# S7G7_footprint_simplified_w_ethernet_v1p.net
KiCad netlist of a schematic drawn in EAGLE
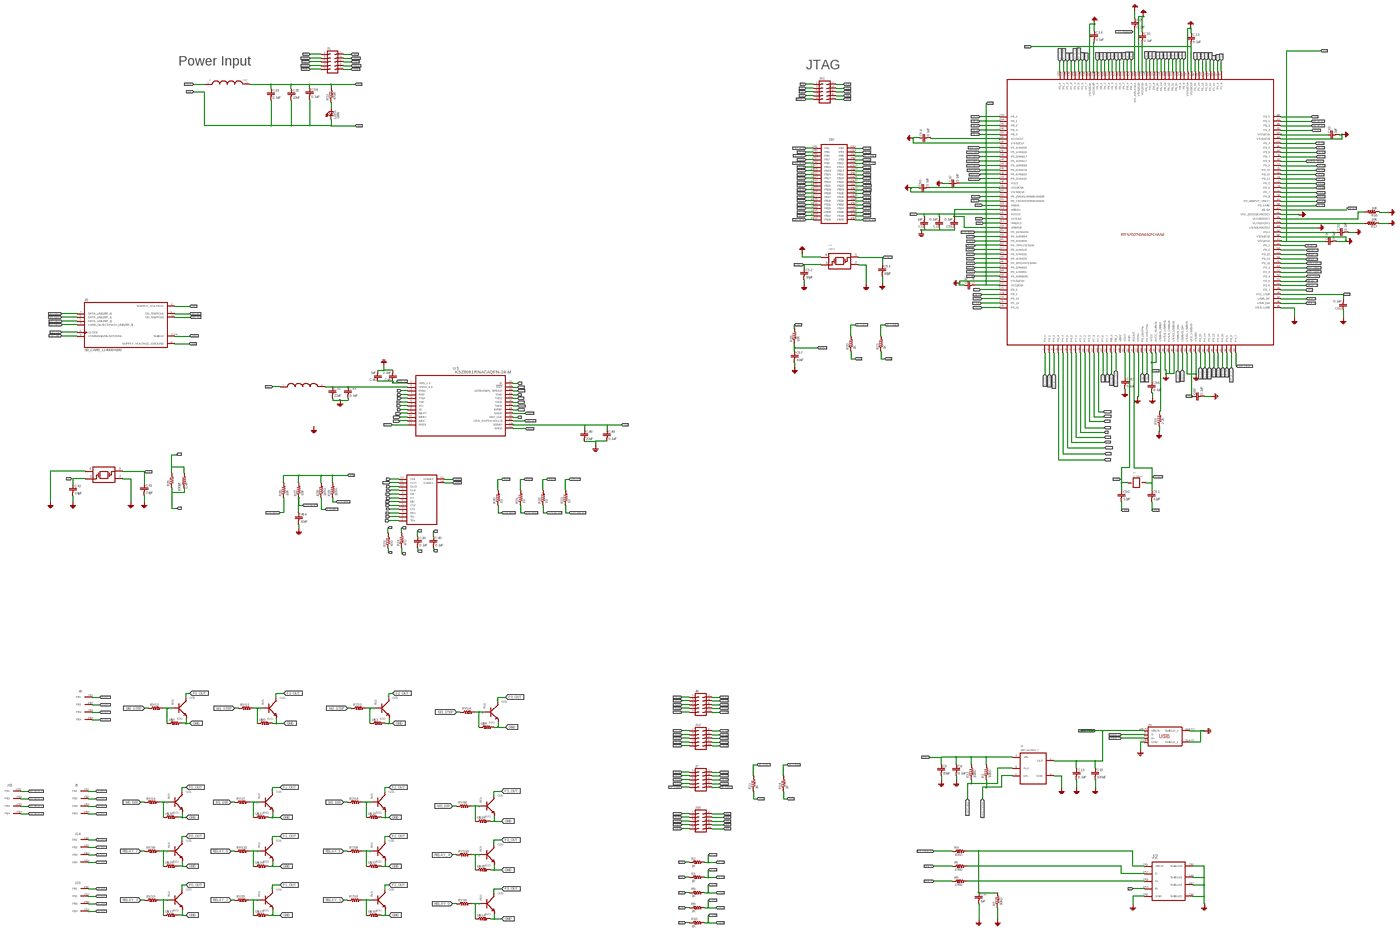
[diagram p0: schematic, sheet 1, overview]
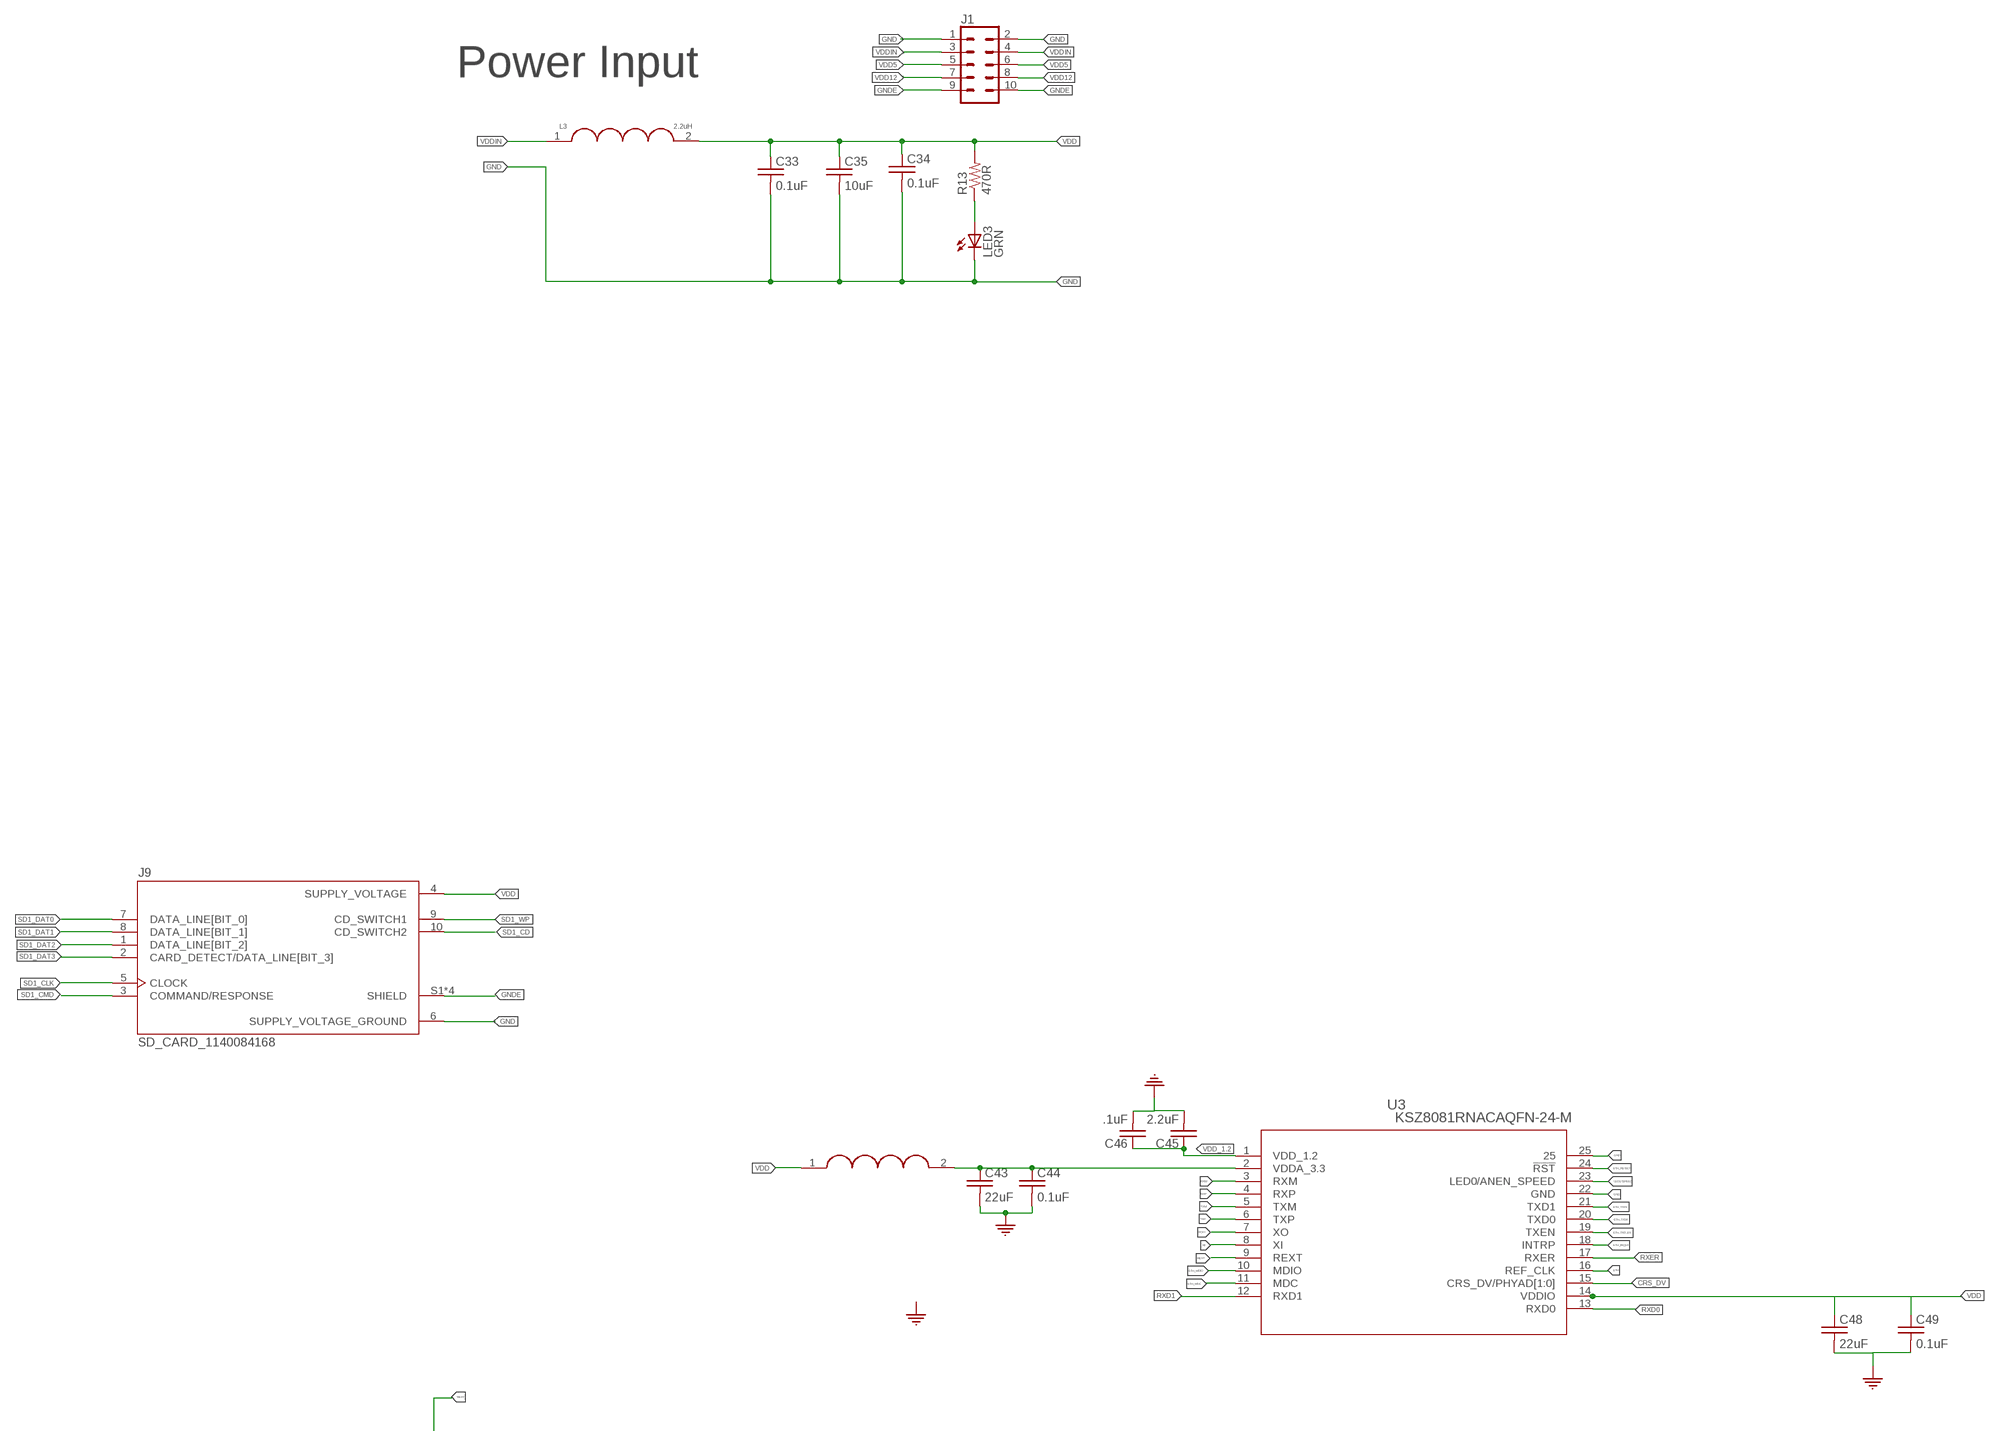
[diagram p1: schematic, sheet 1, part 1 of 4]
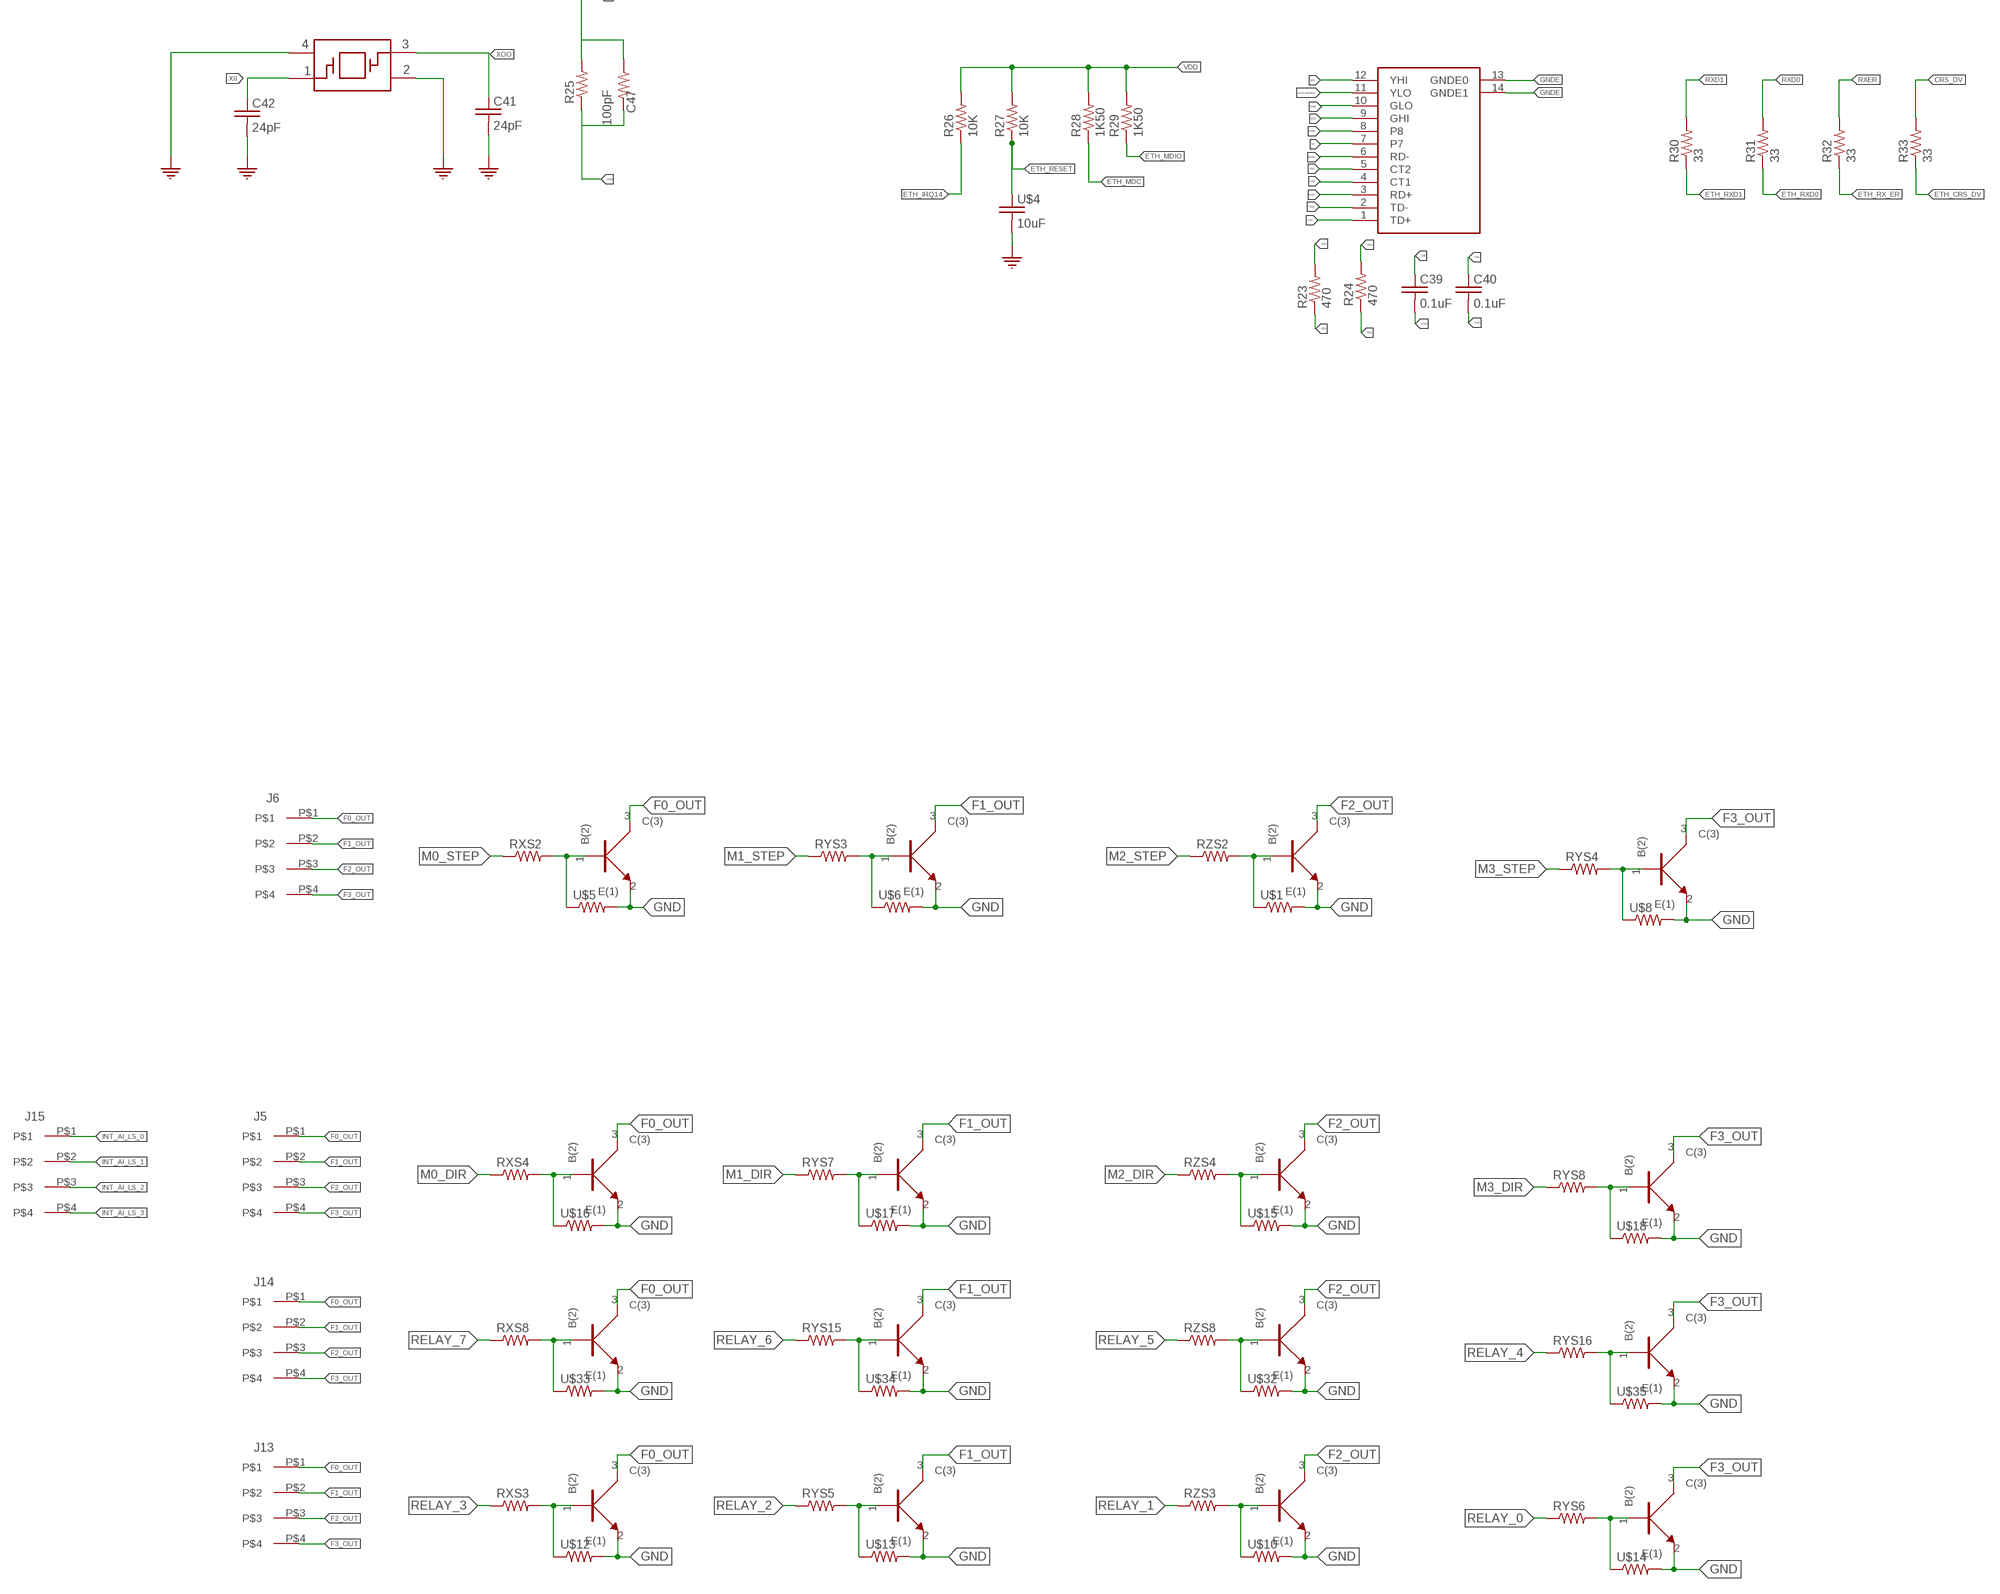
[diagram p2: schematic, sheet 1, part 2 of 4]
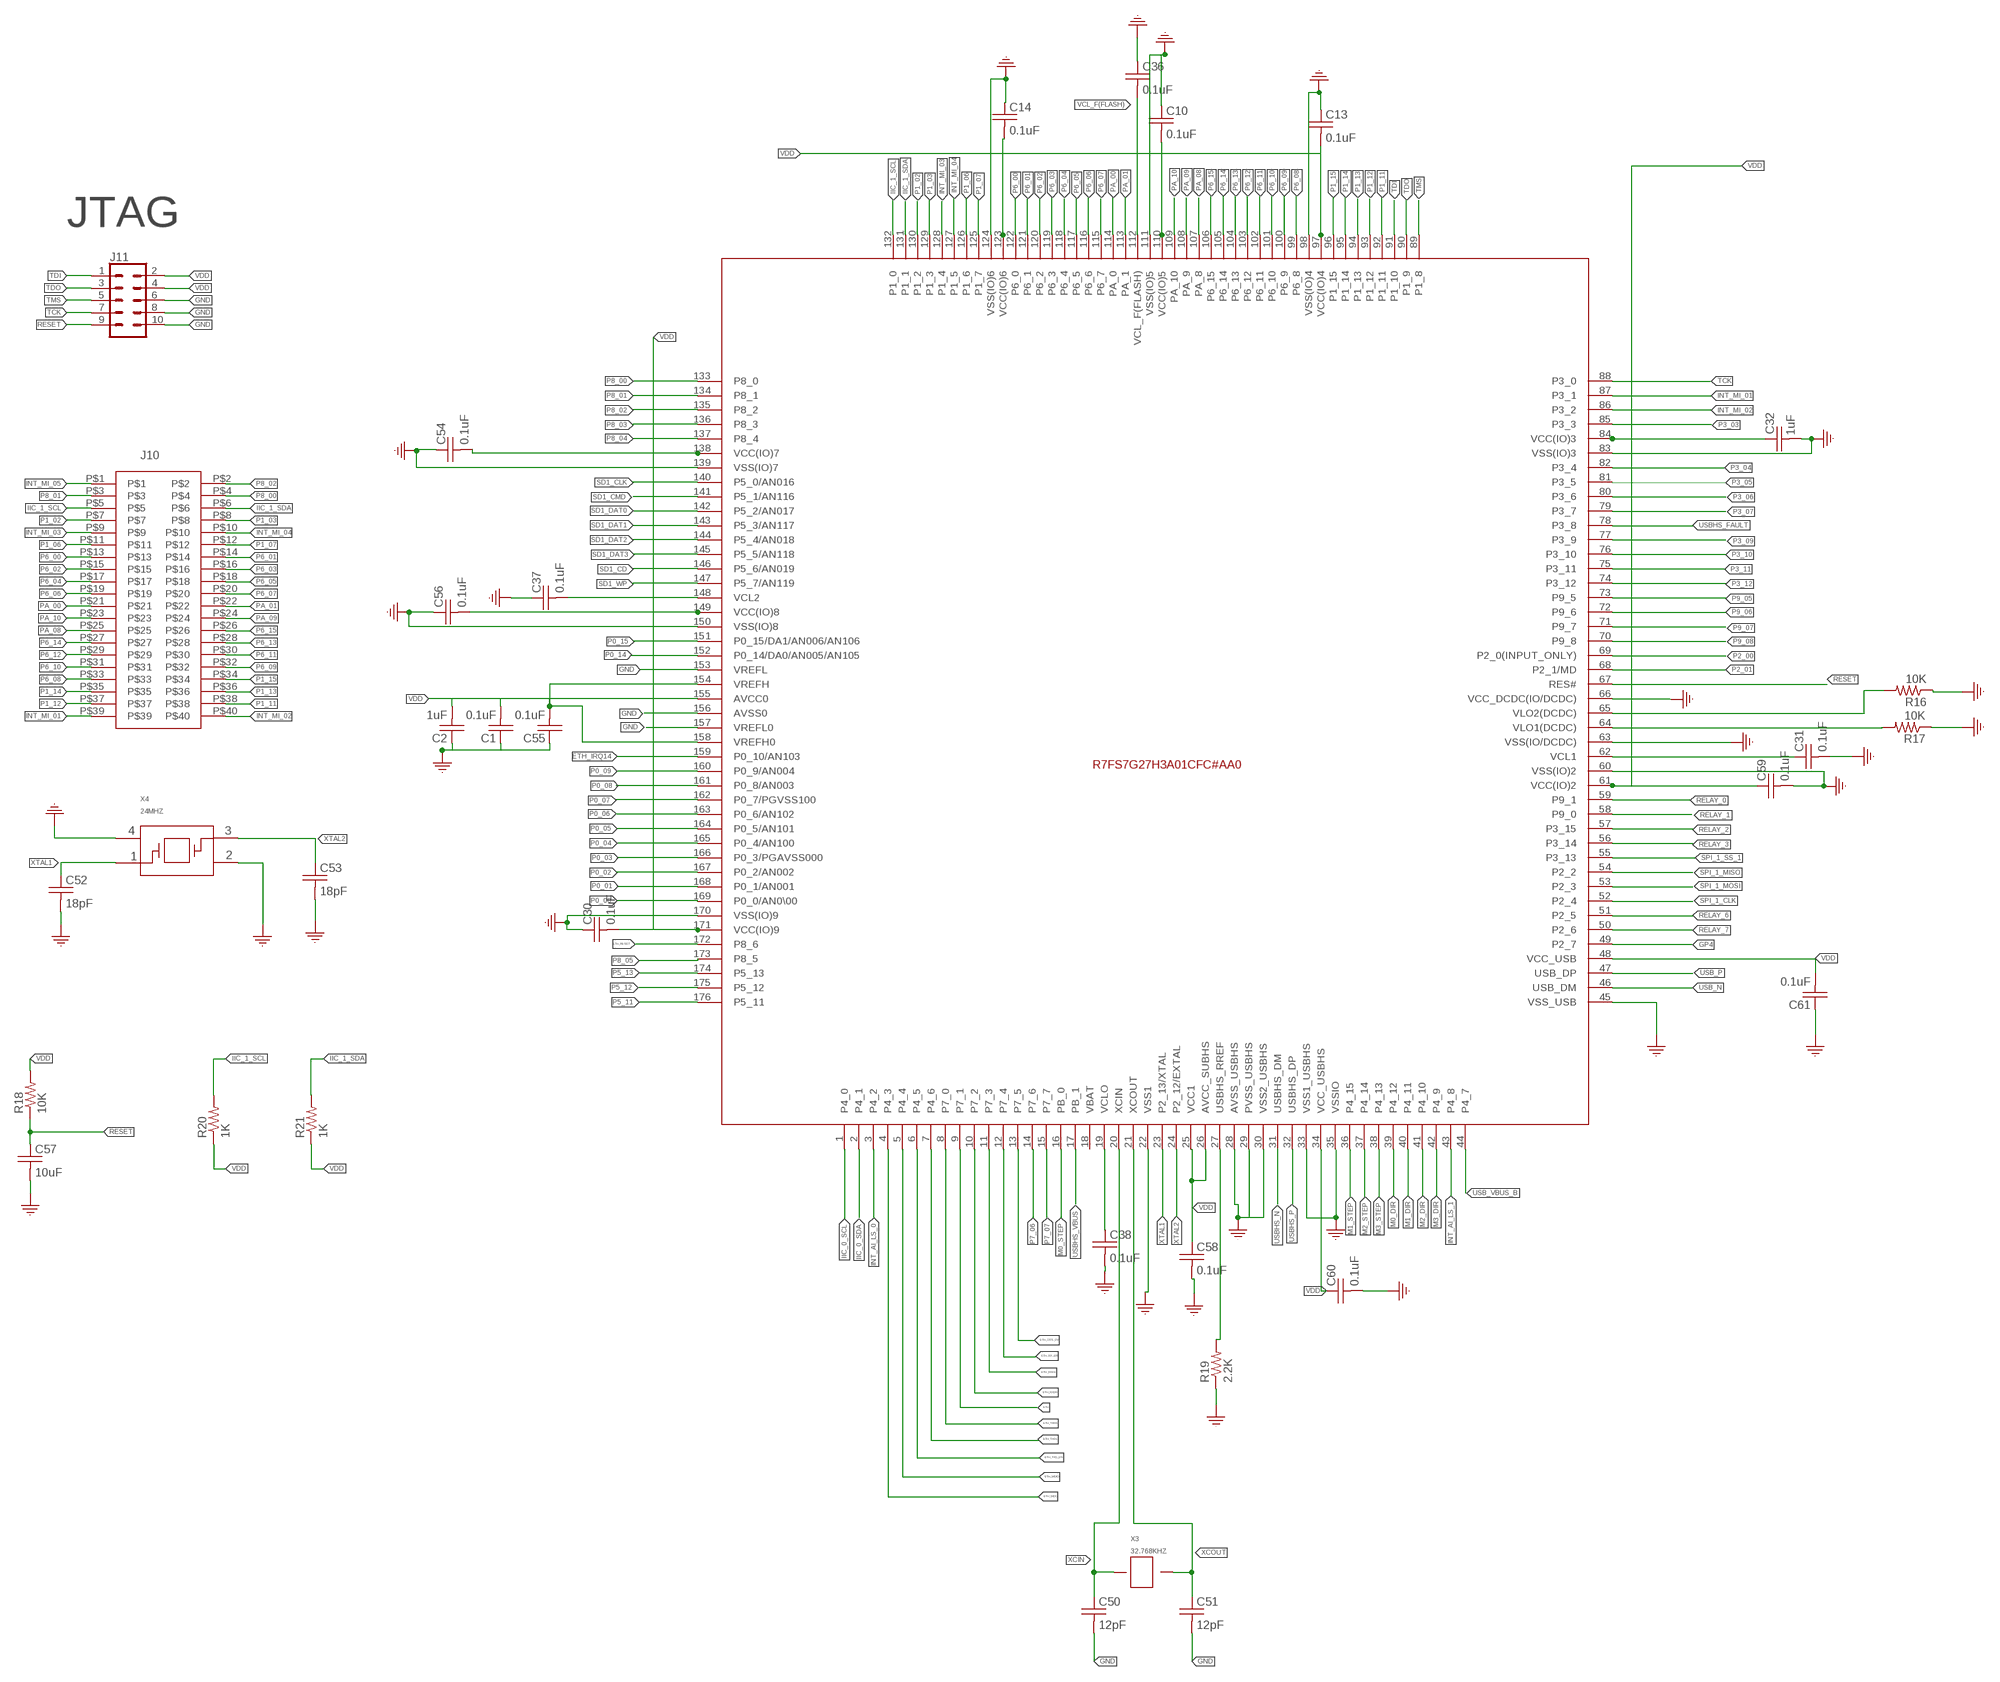
[diagram p3: schematic, sheet 1, part 3 of 4]
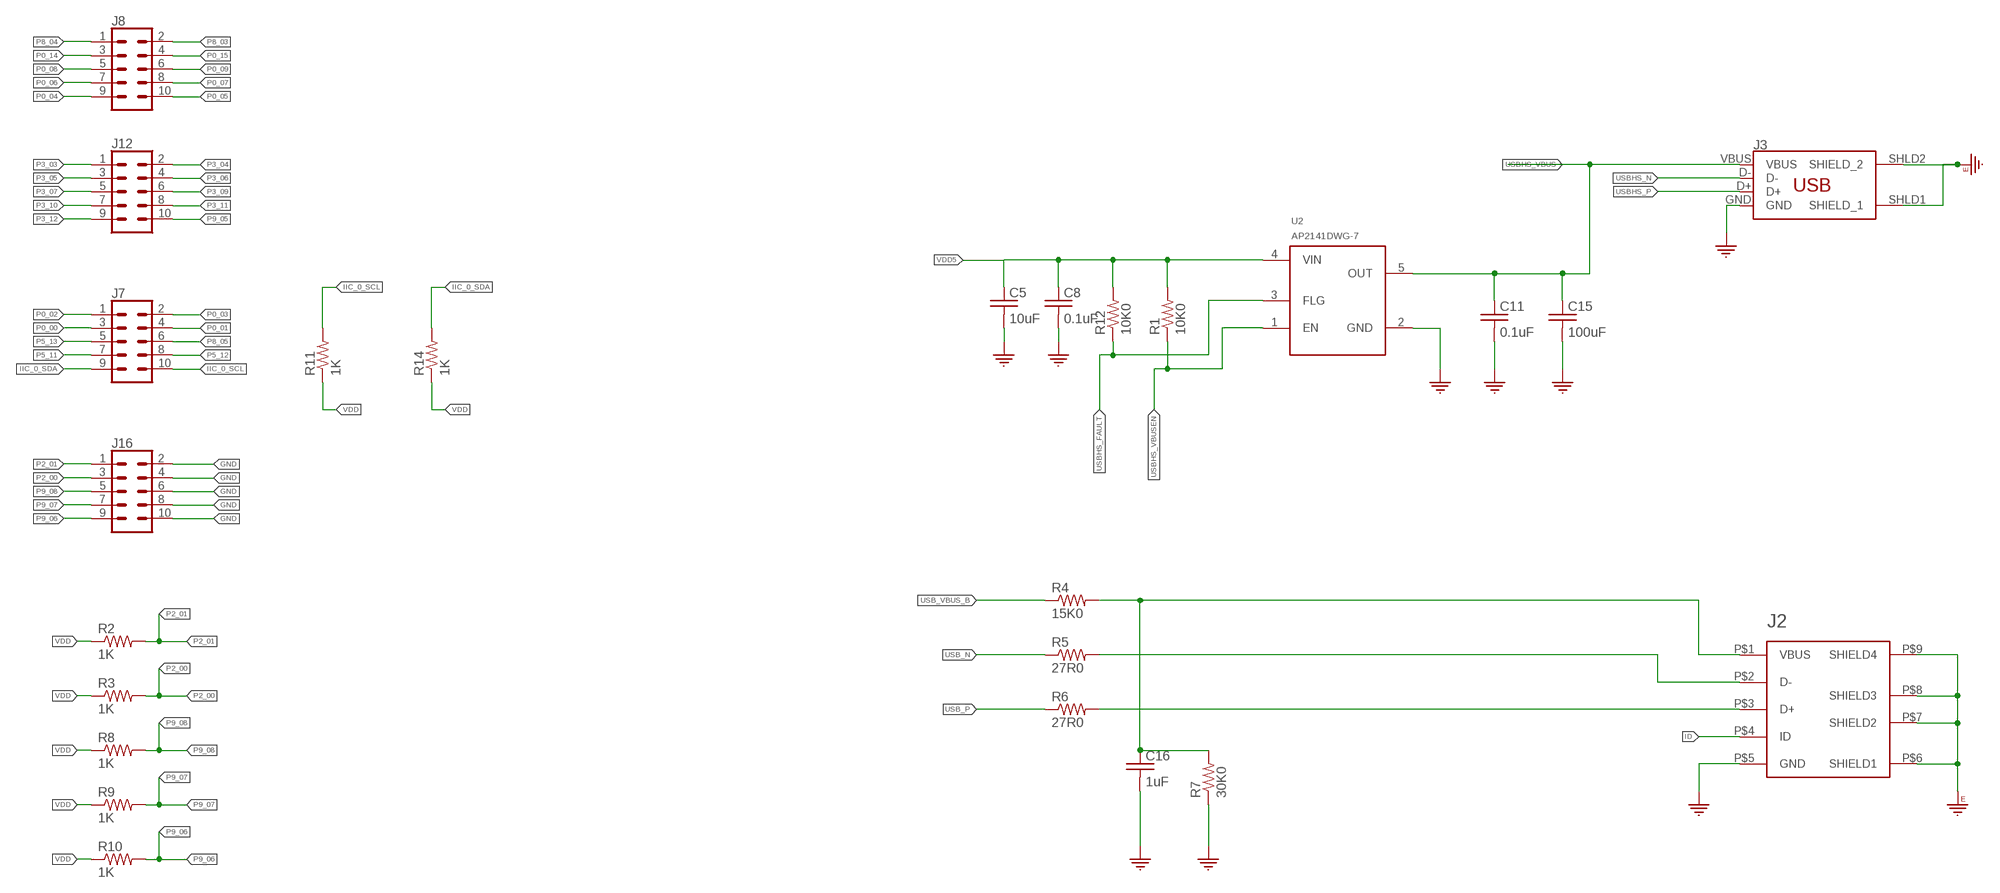
[diagram p4: schematic, sheet 1, part 4 of 4]

(export (version "E")
  (design (tool "Eeschema 10.0.6"))
  (components
    (comp (ref "C1")
      (value "0.1uF")
      (footprint "eagle-import:0402")
      (libsource (lib "eagle-import") (part "C_0402"))
    )
    (comp (ref "C2")
      (value "1uF")
      (footprint "eagle-import:0402")
      (libsource (lib "eagle-import") (part "C_0402"))
    )
    (comp (ref "C5")
      (value "10uF")
      (footprint "eagle-import:0402")
      (libsource (lib "eagle-import") (part "C_0402"))
    )
    (comp (ref "C8")
      (value "0.1uF")
      (footprint "eagle-import:0402")
      (libsource (lib "eagle-import") (part "C_0402"))
    )
    (comp (ref "C10")
      (value "0.1uF")
      (footprint "eagle-import:0402")
      (libsource (lib "eagle-import") (part "C_0402"))
    )
    (comp (ref "C11")
      (value "0.1uF")
      (footprint "eagle-import:0402")
      (libsource (lib "eagle-import") (part "C_0402"))
    )
    (comp (ref "C13")
      (value "0.1uF")
      (footprint "eagle-import:0402")
      (libsource (lib "eagle-import") (part "C_0402"))
    )
    (comp (ref "C14")
      (value "0.1uF")
      (footprint "eagle-import:0402")
      (libsource (lib "eagle-import") (part "C_0402"))
    )
    (comp (ref "C15")
      (value "100uF")
      (footprint "eagle-import:C1210")
      (libsource (lib "eagle-import") (part "C_1210"))
    )
    (comp (ref "C16")
      (value "1uF")
      (footprint "eagle-import:0402")
      (libsource (lib "eagle-import") (part "C_0402"))
    )
    (comp (ref "C30")
      (value "0.1uF")
      (footprint "eagle-import:0402")
      (libsource (lib "eagle-import") (part "C_0402"))
    )
    (comp (ref "C31")
      (value "0.1uF")
      (footprint "eagle-import:0402")
      (libsource (lib "eagle-import") (part "C_0402"))
    )
    (comp (ref "C32")
      (value "1uF")
      (footprint "eagle-import:0402")
      (libsource (lib "eagle-import") (part "C_0402"))
    )
    (comp (ref "C33")
      (value "0.1uF")
      (footprint "eagle-import:0402")
      (libsource (lib "eagle-import") (part "C_0402"))
    )
    (comp (ref "C34")
      (value "0.1uF")
      (footprint "eagle-import:0402")
      (libsource (lib "eagle-import") (part "C_0402"))
    )
    (comp (ref "C35")
      (value "10uF")
      (footprint "eagle-import:0402")
      (libsource (lib "eagle-import") (part "C_0402"))
    )
    (comp (ref "C36")
      (value "0.1uF")
      (footprint "eagle-import:0402")
      (libsource (lib "eagle-import") (part "C_0402"))
    )
    (comp (ref "C37")
      (value "0.1uF")
      (footprint "eagle-import:0402")
      (libsource (lib "eagle-import") (part "C_0402"))
    )
    (comp (ref "C38")
      (value "0.1uF")
      (footprint "eagle-import:0402")
      (libsource (lib "eagle-import") (part "C_0402"))
    )
    (comp (ref "C39")
      (value "0.1uF")
      (footprint "eagle-import:0402")
      (libsource (lib "eagle-import") (part "C_0402"))
    )
    (comp (ref "C40")
      (value "0.1uF")
      (footprint "eagle-import:0402")
      (libsource (lib "eagle-import") (part "C_0402"))
    )
    (comp (ref "C41")
      (value "24pF")
      (footprint "eagle-import:0402")
      (libsource (lib "eagle-import") (part "C_0402"))
    )
    (comp (ref "C42")
      (value "24pF")
      (footprint "eagle-import:0402")
      (libsource (lib "eagle-import") (part "C_0402"))
    )
    (comp (ref "C43")
      (value "22uF")
      (footprint "eagle-import:0603")
      (libsource (lib "eagle-import") (part "C_0603"))
    )
    (comp (ref "C44")
      (value "0.1uF")
      (footprint "eagle-import:0402")
      (libsource (lib "eagle-import") (part "C_0402"))
    )
    (comp (ref "C45")
      (value "2.2uF")
      (footprint "eagle-import:0402")
      (libsource (lib "eagle-import") (part "C_0402"))
    )
    (comp (ref "C46")
      (value ".1uF")
      (footprint "eagle-import:0402")
      (libsource (lib "eagle-import") (part "C_0402"))
    )
    (comp (ref "C47")
      (value "100pF")
      (footprint "eagle-import:0402")
      (libsource (lib "eagle-import") (part "R_0402"))
    )
    (comp (ref "C48")
      (value "22uF")
      (footprint "eagle-import:0603")
      (libsource (lib "eagle-import") (part "C_0603"))
    )
    (comp (ref "C49")
      (value "0.1uF")
      (footprint "eagle-import:0402")
      (libsource (lib "eagle-import") (part "C_0402"))
    )
    (comp (ref "C50")
      (value "12pF")
      (footprint "eagle-import:0402")
      (libsource (lib "eagle-import") (part "C_0402"))
    )
    (comp (ref "C51")
      (value "12pF")
      (footprint "eagle-import:0402")
      (libsource (lib "eagle-import") (part "C_0402"))
    )
    (comp (ref "C52")
      (value "18pF")
      (footprint "eagle-import:0402")
      (libsource (lib "eagle-import") (part "C_0402"))
    )
    (comp (ref "C53")
      (value "18pF")
      (footprint "eagle-import:0402")
      (libsource (lib "eagle-import") (part "C_0402"))
    )
    (comp (ref "C54")
      (value "0.1uF")
      (footprint "eagle-import:0402")
      (libsource (lib "eagle-import") (part "C_0402"))
    )
    (comp (ref "C55")
      (value "0.1uF")
      (footprint "eagle-import:0402")
      (libsource (lib "eagle-import") (part "C_0402"))
    )
    (comp (ref "C56")
      (value "0.1uF")
      (footprint "eagle-import:0402")
      (libsource (lib "eagle-import") (part "C_0402"))
    )
    (comp (ref "C57")
      (value "10uF")
      (footprint "eagle-import:0402")
      (libsource (lib "eagle-import") (part "C_0402"))
    )
    (comp (ref "C58")
      (value "0.1uF")
      (footprint "eagle-import:0402")
      (libsource (lib "eagle-import") (part "C_0402"))
    )
    (comp (ref "C59")
      (value "0.1uF")
      (footprint "eagle-import:0402")
      (libsource (lib "eagle-import") (part "C_0402"))
    )
    (comp (ref "C60")
      (value "0.1uF")
      (footprint "eagle-import:0402")
      (libsource (lib "eagle-import") (part "C_0402"))
    )
    (comp (ref "C61")
      (value "0.1uF")
      (footprint "eagle-import:0402")
      (libsource (lib "eagle-import") (part "C_0402"))
    )
    (comp (ref "FB2/2")
      (value "FB_0805_120_OHM")
      (footprint "eagle-import:0805")
      (libsource (lib "eagle-import") (part "FB_0805_120_OHM"))
    )
    (comp (ref "J1")
      (value "CONN_05X2PTH")
      (footprint "eagle-import:2X5")
      (libsource (lib "eagle-import") (part "CONN_05X2PTH"))
    )
    (comp (ref "J2")
      (value "USB_MICRO-B")
      (footprint "eagle-import:USB_MICRO-B")
      (libsource (lib "eagle-import") (part "USB_MICRO-B"))
    )
    (comp (ref "J3")
      (value "USB_A")
      (footprint "eagle-import:USB_A_SMT")
      (libsource (lib "eagle-import") (part "USB_A"))
    )
    (comp (ref "J4")
      (value "RJ45_WITH_ELEC")
      (footprint "eagle-import:RJ45_TH_ELEC")
      (libsource (lib "eagle-import") (part "RJ45_WITH_ELEC"))
    )
    (comp (ref "J5")
      (value "3.81MM_1_X_4_RT_ANGLE_PLUG_HEADER")
      (footprint "eagle-import:1X4_3.81MM_PITCH")
      (libsource (lib "eagle-import") (part "3.81MM_1_X_4_RT_ANGLE_PLUG_HEADER"))
    )
    (comp (ref "J6")
      (value "3.81MM_1_X_4_RT_ANGLE_PLUG_HEADER")
      (footprint "eagle-import:1X4_3.81MM_PITCH")
      (libsource (lib "eagle-import") (part "3.81MM_1_X_4_RT_ANGLE_PLUG_HEADER"))
    )
    (comp (ref "J7")
      (value "CONN_05X2NO_SILK")
      (footprint "eagle-import:2X5_NOSILK")
      (libsource (lib "eagle-import") (part "CONN_05X2NO_SILK"))
    )
    (comp (ref "J8")
      (value "CONN_05X2NO_SILK")
      (footprint "eagle-import:2X5_NOSILK")
      (libsource (lib "eagle-import") (part "CONN_05X2NO_SILK"))
    )
    (comp (ref "J9")
      (value "SD_CARD_1140084168")
      (footprint "eagle-import:AMPHENOL_1140084168")
      (fields
        (field (name "DIGI-KEY_PART_NUMBER") "114-00841-68-1-ND")
        (field (name "MF") "Amphenol ICC")
        (field (name "MP") "114-00841-68")
      )
      (libsource (lib "eagle-import") (part "SD_CARD_1140084168"))
    )
    (comp (ref "J10")
      (value "HEADER_2_X_20_GENERIC")
      (footprint "eagle-import:HEADER_2_X_20_.1_INCH")
      (libsource (lib "eagle-import") (part "HEADER_2_X_20_GENERIC"))
    )
    (comp (ref "J11")
      (value "CONN_05X2PTH")
      (footprint "eagle-import:2X5")
      (libsource (lib "eagle-import") (part "CONN_05X2PTH"))
    )
    (comp (ref "J12")
      (value "CONN_05X2NO_SILK")
      (footprint "eagle-import:2X5_NOSILK")
      (libsource (lib "eagle-import") (part "CONN_05X2NO_SILK"))
    )
    (comp (ref "J13")
      (value "3.81MM_1_X_4_RT_ANGLE_PLUG_HEADER")
      (footprint "eagle-import:1X4_3.81MM_PITCH")
      (libsource (lib "eagle-import") (part "3.81MM_1_X_4_RT_ANGLE_PLUG_HEADER"))
    )
    (comp (ref "J14")
      (value "3.81MM_1_X_4_RT_ANGLE_PLUG_HEADER")
      (footprint "eagle-import:1X4_3.81MM_PITCH")
      (libsource (lib "eagle-import") (part "3.81MM_1_X_4_RT_ANGLE_PLUG_HEADER"))
    )
    (comp (ref "J15")
      (value "3.81MM_1_X_4_RT_ANGLE_PLUG_HEADER")
      (footprint "eagle-import:1X4_3.81MM_PITCH")
      (libsource (lib "eagle-import") (part "3.81MM_1_X_4_RT_ANGLE_PLUG_HEADER"))
    )
    (comp (ref "J16")
      (value "CONN_05X2SHD_SMD")
      (footprint "eagle-import:2X5-SHROUDED_SMD")
      (libsource (lib "eagle-import") (part "CONN_05X2SHD_SMD"))
    )
    (comp (ref "L3")
      (value "2.2uH")
      (footprint "eagle-import:1008_(2520_METRIC)")
      (libsource (lib "eagle-import") (part "INDUCTOR_1008_2.2_MH_1.3A"))
    )
    (comp (ref "LED3")
      (value "LED_0805_GREEN")
      (footprint "eagle-import:LED_0805_GREEN")
      (libsource (lib "eagle-import") (part "LED_0805_GREEN"))
    )
    (comp (ref "R1")
      (value "10K0")
      (footprint "eagle-import:0402")
      (libsource (lib "eagle-import") (part "R_0402"))
    )
    (comp (ref "R2")
      (value "1K")
      (footprint "eagle-import:0402")
      (libsource (lib "eagle-import") (part "R_0402"))
    )
    (comp (ref "R3")
      (value "1K")
      (footprint "eagle-import:0402")
      (libsource (lib "eagle-import") (part "R_0402"))
    )
    (comp (ref "R4")
      (value "15K0")
      (footprint "eagle-import:0402")
      (libsource (lib "eagle-import") (part "R_0402"))
    )
    (comp (ref "R5")
      (value "27R0")
      (footprint "eagle-import:0402")
      (libsource (lib "eagle-import") (part "R_0402"))
    )
    (comp (ref "R6")
      (value "27R0")
      (footprint "eagle-import:0402")
      (libsource (lib "eagle-import") (part "R_0402"))
    )
    (comp (ref "R7")
      (value "30K0")
      (footprint "eagle-import:0402")
      (libsource (lib "eagle-import") (part "R_0402"))
    )
    (comp (ref "R8")
      (value "1K")
      (footprint "eagle-import:0402")
      (libsource (lib "eagle-import") (part "R_0402"))
    )
    (comp (ref "R9")
      (value "1K")
      (footprint "eagle-import:0402")
      (libsource (lib "eagle-import") (part "R_0402"))
    )
    (comp (ref "R10")
      (value "1K")
      (footprint "eagle-import:0402")
      (libsource (lib "eagle-import") (part "R_0402"))
    )
    (comp (ref "R11")
      (value "1K")
      (footprint "eagle-import:0402")
      (libsource (lib "eagle-import") (part "R_0402"))
    )
    (comp (ref "R12")
      (value "10K0")
      (footprint "eagle-import:0402")
      (libsource (lib "eagle-import") (part "R_0402"))
    )
    (comp (ref "R13")
      (value "470R")
      (footprint "eagle-import:0402")
      (libsource (lib "eagle-import") (part "R_0402"))
    )
    (comp (ref "R14")
      (value "1K")
      (footprint "eagle-import:0402")
      (libsource (lib "eagle-import") (part "R_0402"))
    )
    (comp (ref "R16")
      (value "10K")
      (footprint "eagle-import:0402")
      (libsource (lib "eagle-import") (part "R_0402"))
    )
    (comp (ref "R17")
      (value "10K")
      (footprint "eagle-import:0402")
      (libsource (lib "eagle-import") (part "R_0402"))
    )
    (comp (ref "R18")
      (value "10K")
      (footprint "eagle-import:0402")
      (libsource (lib "eagle-import") (part "R_0402"))
    )
    (comp (ref "R19")
      (value "2.2K")
      (footprint "eagle-import:0402")
      (libsource (lib "eagle-import") (part "R_0402"))
    )
    (comp (ref "R20")
      (value "1K")
      (footprint "eagle-import:0402")
      (libsource (lib "eagle-import") (part "R_0402"))
    )
    (comp (ref "R21")
      (value "1K")
      (footprint "eagle-import:0402")
      (libsource (lib "eagle-import") (part "R_0402"))
    )
    (comp (ref "R23")
      (value "470")
      (footprint "eagle-import:0402")
      (libsource (lib "eagle-import") (part "R_0402"))
    )
    (comp (ref "R24")
      (value "470")
      (footprint "eagle-import:0402")
      (libsource (lib "eagle-import") (part "R_0402"))
    )
    (comp (ref "R25")
      (value "6k49")
      (footprint "eagle-import:0402")
      (libsource (lib "eagle-import") (part "R_0402"))
    )
    (comp (ref "R26")
      (value "10K")
      (footprint "eagle-import:0402")
      (libsource (lib "eagle-import") (part "R_0402"))
    )
    (comp (ref "R27")
      (value "10K")
      (footprint "eagle-import:0402")
      (libsource (lib "eagle-import") (part "R_0402"))
    )
    (comp (ref "R28")
      (value "1K50")
      (footprint "eagle-import:0402")
      (libsource (lib "eagle-import") (part "R_0402"))
    )
    (comp (ref "R29")
      (value "1K50")
      (footprint "eagle-import:0402")
      (libsource (lib "eagle-import") (part "R_0402"))
    )
    (comp (ref "R30")
      (value "33")
      (footprint "eagle-import:0402")
      (libsource (lib "eagle-import") (part "R_0402"))
    )
    (comp (ref "R31")
      (value "33")
      (footprint "eagle-import:0402")
      (libsource (lib "eagle-import") (part "R_0402"))
    )
    (comp (ref "R32")
      (value "33")
      (footprint "eagle-import:0402")
      (libsource (lib "eagle-import") (part "R_0402"))
    )
    (comp (ref "R33")
      (value "33")
      (footprint "eagle-import:0402")
      (libsource (lib "eagle-import") (part "R_0402"))
    )
    (comp (ref "RXS2")
      (value "1K")
      (footprint "eagle-import:0402")
      (libsource (lib "eagle-import") (part "R_0402"))
    )
    (comp (ref "RXS3")
      (value "1K")
      (footprint "eagle-import:0402")
      (libsource (lib "eagle-import") (part "R_0402"))
    )
    (comp (ref "RXS4")
      (value "1K")
      (footprint "eagle-import:0402")
      (libsource (lib "eagle-import") (part "R_0402"))
    )
    (comp (ref "RXS8")
      (value "1K")
      (footprint "eagle-import:0402")
      (libsource (lib "eagle-import") (part "R_0402"))
    )
    (comp (ref "RYS3")
      (value "1K")
      (footprint "eagle-import:0402")
      (libsource (lib "eagle-import") (part "R_0402"))
    )
    (comp (ref "RYS4")
      (value "1K")
      (footprint "eagle-import:0402")
      (libsource (lib "eagle-import") (part "R_0402"))
    )
    (comp (ref "RYS5")
      (value "1K")
      (footprint "eagle-import:0402")
      (libsource (lib "eagle-import") (part "R_0402"))
    )
    (comp (ref "RYS6")
      (value "1K")
      (footprint "eagle-import:0402")
      (libsource (lib "eagle-import") (part "R_0402"))
    )
    (comp (ref "RYS7")
      (value "1K")
      (footprint "eagle-import:0402")
      (libsource (lib "eagle-import") (part "R_0402"))
    )
    (comp (ref "RYS8")
      (value "1K")
      (footprint "eagle-import:0402")
      (libsource (lib "eagle-import") (part "R_0402"))
    )
    (comp (ref "RYS15")
      (value "1K")
      (footprint "eagle-import:0402")
      (libsource (lib "eagle-import") (part "R_0402"))
    )
    (comp (ref "RYS16")
      (value "1K")
      (footprint "eagle-import:0402")
      (libsource (lib "eagle-import") (part "R_0402"))
    )
    (comp (ref "RZS2")
      (value "1K")
      (footprint "eagle-import:0402")
      (libsource (lib "eagle-import") (part "R_0402"))
    )
    (comp (ref "RZS3")
      (value "1K")
      (footprint "eagle-import:0402")
      (libsource (lib "eagle-import") (part "R_0402"))
    )
    (comp (ref "RZS4")
      (value "1K")
      (footprint "eagle-import:0402")
      (libsource (lib "eagle-import") (part "R_0402"))
    )
    (comp (ref "RZS8")
      (value "1K")
      (footprint "eagle-import:0402")
      (libsource (lib "eagle-import") (part "R_0402"))
    )
    (comp (ref "U$1")
      (value "1K")
      (footprint "eagle-import:0402")
      (libsource (lib "eagle-import") (part "R_0402"))
    )
    (comp (ref "U$3")
      (value "XTAL_25_MHZ")
      (footprint "eagle-import:SMD_3225")
      (libsource (lib "eagle-import") (part "XTAL_25_MHZ"))
    )
    (comp (ref "U$4")
      (value "10uF")
      (footprint "eagle-import:0402")
      (libsource (lib "eagle-import") (part "C_0402"))
    )
    (comp (ref "U$5")
      (value "1K")
      (footprint "eagle-import:0402")
      (libsource (lib "eagle-import") (part "R_0402"))
    )
    (comp (ref "U$6")
      (value "1K")
      (footprint "eagle-import:0402")
      (libsource (lib "eagle-import") (part "R_0402"))
    )
    (comp (ref "U$8")
      (value "1K")
      (footprint "eagle-import:0402")
      (libsource (lib "eagle-import") (part "R_0402"))
    )
    (comp (ref "U$10")
      (value "1K")
      (footprint "eagle-import:0402")
      (libsource (lib "eagle-import") (part "R_0402"))
    )
    (comp (ref "U$12")
      (value "1K")
      (footprint "eagle-import:0402")
      (libsource (lib "eagle-import") (part "R_0402"))
    )
    (comp (ref "U$13")
      (value "1K")
      (footprint "eagle-import:0402")
      (libsource (lib "eagle-import") (part "R_0402"))
    )
    (comp (ref "U$14")
      (value "1K")
      (footprint "eagle-import:0402")
      (libsource (lib "eagle-import") (part "R_0402"))
    )
    (comp (ref "U$15")
      (value "1K")
      (footprint "eagle-import:0402")
      (libsource (lib "eagle-import") (part "R_0402"))
    )
    (comp (ref "U$16")
      (value "1K")
      (footprint "eagle-import:0402")
      (libsource (lib "eagle-import") (part "R_0402"))
    )
    (comp (ref "U$17")
      (value "1K")
      (footprint "eagle-import:0402")
      (libsource (lib "eagle-import") (part "R_0402"))
    )
    (comp (ref "U$18")
      (value "1K")
      (footprint "eagle-import:0402")
      (libsource (lib "eagle-import") (part "R_0402"))
    )
    (comp (ref "U$32")
      (value "1K")
      (footprint "eagle-import:0402")
      (libsource (lib "eagle-import") (part "R_0402"))
    )
    (comp (ref "U$33")
      (value "1K")
      (footprint "eagle-import:0402")
      (libsource (lib "eagle-import") (part "R_0402"))
    )
    (comp (ref "U$34")
      (value "1K")
      (footprint "eagle-import:0402")
      (libsource (lib "eagle-import") (part "R_0402"))
    )
    (comp (ref "U$35")
      (value "1K")
      (footprint "eagle-import:0402")
      (libsource (lib "eagle-import") (part "R_0402"))
    )
    (comp (ref "U2")
      (value "AP2141DWG-5")
      (footprint "eagle-import:SOT-23-5")
      (libsource (lib "eagle-import") (part "AP2141DWG-5"))
    )
    (comp (ref "U3")
      (value "KSZ8081RNACAQFN-24-M")
      (footprint "eagle-import:QFN-24-M")
      (fields (field (name "MANUFACTURER_PART_NUMBER") "KSZ8081RNACA"))
      (libsource (lib "eagle-import") (part "KSZ8081RNACAQFN-24-M"))
    )
    (comp (ref "U4")
      (value "S7G2_X_176")
      (footprint "eagle-import:LQFP176_24X24")
      (libsource (lib "eagle-import") (part "S7G2_X_176"))
    )
    (comp (ref "U7")
      (value "BC846BW")
      (footprint "eagle-import:SOT323")
      (libsource (lib "eagle-import") (part "BC846BW"))
    )
    (comp (ref "U8")
      (value "BC846BW")
      (footprint "eagle-import:SOT323")
      (libsource (lib "eagle-import") (part "BC846BW"))
    )
    (comp (ref "U9")
      (value "BC846BW")
      (footprint "eagle-import:SOT323")
      (libsource (lib "eagle-import") (part "BC846BW"))
    )
    (comp (ref "U10")
      (value "BC846BW")
      (footprint "eagle-import:SOT323")
      (libsource (lib "eagle-import") (part "BC846BW"))
    )
    (comp (ref "U12")
      (value "BC846BW")
      (footprint "eagle-import:SOT323")
      (libsource (lib "eagle-import") (part "BC846BW"))
    )
    (comp (ref "U13")
      (value "BC846BW")
      (footprint "eagle-import:SOT323")
      (libsource (lib "eagle-import") (part "BC846BW"))
    )
    (comp (ref "U14")
      (value "BC846BW")
      (footprint "eagle-import:SOT323")
      (libsource (lib "eagle-import") (part "BC846BW"))
    )
    (comp (ref "U15")
      (value "BC846BW")
      (footprint "eagle-import:SOT323")
      (libsource (lib "eagle-import") (part "BC846BW"))
    )
    (comp (ref "U16")
      (value "BC846BW")
      (footprint "eagle-import:SOT323")
      (libsource (lib "eagle-import") (part "BC846BW"))
    )
    (comp (ref "U17")
      (value "BC846BW")
      (footprint "eagle-import:SOT323")
      (libsource (lib "eagle-import") (part "BC846BW"))
    )
    (comp (ref "U18")
      (value "BC846BW")
      (footprint "eagle-import:SOT323")
      (libsource (lib "eagle-import") (part "BC846BW"))
    )
    (comp (ref "U19")
      (value "BC846BW")
      (footprint "eagle-import:SOT323")
      (libsource (lib "eagle-import") (part "BC846BW"))
    )
    (comp (ref "U32")
      (value "BC846BW")
      (footprint "eagle-import:SOT323")
      (libsource (lib "eagle-import") (part "BC846BW"))
    )
    (comp (ref "U33")
      (value "BC846BW")
      (footprint "eagle-import:SOT323")
      (libsource (lib "eagle-import") (part "BC846BW"))
    )
    (comp (ref "U34")
      (value "BC846BW")
      (footprint "eagle-import:SOT323")
      (libsource (lib "eagle-import") (part "BC846BW"))
    )
    (comp (ref "U35")
      (value "BC846BW")
      (footprint "eagle-import:SOT323")
      (libsource (lib "eagle-import") (part "BC846BW"))
    )
    (comp (ref "X3")
      (value "32.768KHZ")
      (footprint "eagle-import:SMD_X_2_PADS")
      (libsource (lib "eagle-import") (part "XTAL_32.768KHZ"))
    )
    (comp (ref "X4")
      (value "24MHZ")
      (footprint "eagle-import:SMD_3225")
      (libsource (lib "eagle-import") (part "XTAL_24_MHZ"))
    )
  )
  (nets
    (net (code "1") (name "C58") (class "Default")
      (node (ref "C39") (pin "P$1") (pinfunction "1_P$1") (pintype "passive"))
      (node (ref "J4") (pin "4") (pinfunction "CT1_4") (pintype "bidirectional"))
    )
    (net (code "2") (name "C60") (class "Default")
      (node (ref "C40") (pin "P$1") (pinfunction "1_P$1") (pintype "passive"))
      (node (ref "J4") (pin "5") (pinfunction "CT2_5") (pintype "bidirectional"))
    )
    (net (code "3") (name "CRS_DV") (class "Default")
      (node (ref "R33") (pin "P$2") (pinfunction "2_P$2") (pintype "passive"))
      (node (ref "U3") (pin "15") (pinfunction "CRS_DV/PHYAD[1:0]_15") (pintype "bidirectional"))
    )
    (net (code "4") (name "ETH") (class "Default")
      (node (ref "U3") (pin "16") (pinfunction "REF_CLK_16") (pintype "bidirectional"))
      (node (ref "U4") (pin "9") (pinfunction "P7_1_9") (pintype "bidirectional"))
    )
    (net (code "5") (name "ETH_CRS_DV") (class "Default")
      (node (ref "R33") (pin "P$1") (pinfunction "1_P$1") (pintype "passive"))
      (node (ref "U4") (pin "13") (pinfunction "P7_5_13") (pintype "bidirectional"))
    )
    (net (code "6") (name "ETH_IRQ14") (class "Default")
      (node (ref "R26") (pin "P$1") (pinfunction "1_P$1") (pintype "passive"))
      (node (ref "U3") (pin "18") (pinfunction "INTRP_18") (pintype "bidirectional"))
      (node (ref "U4") (pin "159") (pinfunction "P0_10/AN103_159") (pintype "bidirectional"))
    )
    (net (code "7") (name "ETH_MDC") (class "Default")
      (node (ref "R28") (pin "P$1") (pinfunction "1_P$1") (pintype "passive"))
      (node (ref "U3") (pin "11") (pinfunction "MDC_11") (pintype "input"))
      (node (ref "U4") (pin "4") (pinfunction "P4_3_4") (pintype "bidirectional"))
    )
    (net (code "8") (name "ETH_MDIO") (class "Default")
      (node (ref "R29") (pin "P$1") (pinfunction "1_P$1") (pintype "passive"))
      (node (ref "U3") (pin "10") (pinfunction "MDIO_10") (pintype "bidirectional"))
      (node (ref "U4") (pin "5") (pinfunction "P4_4_5") (pintype "bidirectional"))
    )
    (net (code "9") (name "ETH_RESET") (class "Default")
      (node (ref "R27") (pin "P$1") (pinfunction "1_P$1") (pintype "passive"))
      (node (ref "U$4") (pin "P$1") (pinfunction "1_P$1") (pintype "passive"))
      (node (ref "U3") (pin "24") (pinfunction "~{RST}_24") (pintype "input"))
      (node (ref "U4") (pin "172") (pinfunction "P8_6_172") (pintype "bidirectional"))
    )
    (net (code "10") (name "ETH_RXD0") (class "Default")
      (node (ref "R31") (pin "P$1") (pinfunction "1_P$1") (pintype "passive"))
      (node (ref "U4") (pin "10") (pinfunction "P7_2_10") (pintype "bidirectional"))
    )
    (net (code "11") (name "ETH_RXD1") (class "Default")
      (node (ref "R30") (pin "P$1") (pinfunction "1_P$1") (pintype "passive"))
      (node (ref "U4") (pin "11") (pinfunction "P7_3_11") (pintype "bidirectional"))
    )
    (net (code "12") (name "ETH_RX_ER") (class "Default")
      (node (ref "R32") (pin "P$1") (pinfunction "1_P$1") (pintype "passive"))
      (node (ref "U4") (pin "12") (pinfunction "P7_4_12") (pintype "bidirectional"))
    )
    (net (code "13") (name "ETH_TXD0") (class "Default")
      (node (ref "U3") (pin "20") (pinfunction "TXD0_20") (pintype "input"))
      (node (ref "U4") (pin "8") (pinfunction "P7_0_8") (pintype "bidirectional"))
    )
    (net (code "14") (name "ETH_TXD1") (class "Default")
      (node (ref "U3") (pin "21") (pinfunction "TXD1_21") (pintype "bidirectional"))
      (node (ref "U4") (pin "7") (pinfunction "P4_6_7") (pintype "bidirectional"))
    )
    (net (code "15") (name "ETH_TXD_EN") (class "Default")
      (node (ref "U3") (pin "19") (pinfunction "TXEN_19") (pintype "input"))
      (node (ref "U4") (pin "6") (pinfunction "P4_5_6") (pintype "bidirectional"))
    )
    (net (code "16") (name "F0_OUT") (class "Default")
      (node (ref "J13") (pin "P$1") (pinfunction "P$1_P$1") (pintype "bidirectional"))
      (node (ref "J14") (pin "P$1") (pinfunction "P$1_P$1") (pintype "bidirectional"))
      (node (ref "J5") (pin "P$1") (pinfunction "P$1_P$1") (pintype "bidirectional"))
      (node (ref "J6") (pin "P$1") (pinfunction "P$1_P$1") (pintype "bidirectional"))
      (node (ref "U13") (pin "3") (pinfunction "C(3)_3") (pintype "input"))
      (node (ref "U17") (pin "3") (pinfunction "C(3)_3") (pintype "input"))
      (node (ref "U33") (pin "3") (pinfunction "C(3)_3") (pintype "input"))
      (node (ref "U8") (pin "3") (pinfunction "C(3)_3") (pintype "input"))
    )
    (net (code "17") (name "F1_OUT") (class "Default")
      (node (ref "J13") (pin "P$2") (pinfunction "P$2_P$2") (pintype "bidirectional"))
      (node (ref "J14") (pin "P$2") (pinfunction "P$2_P$2") (pintype "bidirectional"))
      (node (ref "J5") (pin "P$2") (pinfunction "P$2_P$2") (pintype "bidirectional"))
      (node (ref "J6") (pin "P$2") (pinfunction "P$2_P$2") (pintype "bidirectional"))
      (node (ref "U14") (pin "3") (pinfunction "C(3)_3") (pintype "input"))
      (node (ref "U18") (pin "3") (pinfunction "C(3)_3") (pintype "input"))
      (node (ref "U34") (pin "3") (pinfunction "C(3)_3") (pintype "input"))
      (node (ref "U9") (pin "3") (pinfunction "C(3)_3") (pintype "input"))
    )
    (net (code "18") (name "F2_OUT") (class "Default")
      (node (ref "J13") (pin "P$3") (pinfunction "P$3_P$3") (pintype "bidirectional"))
      (node (ref "J14") (pin "P$3") (pinfunction "P$3_P$3") (pintype "bidirectional"))
      (node (ref "J5") (pin "P$3") (pinfunction "P$3_P$3") (pintype "bidirectional"))
      (node (ref "J6") (pin "P$3") (pinfunction "P$3_P$3") (pintype "bidirectional"))
      (node (ref "U12") (pin "3") (pinfunction "C(3)_3") (pintype "input"))
      (node (ref "U16") (pin "3") (pinfunction "C(3)_3") (pintype "input"))
      (node (ref "U32") (pin "3") (pinfunction "C(3)_3") (pintype "input"))
      (node (ref "U7") (pin "3") (pinfunction "C(3)_3") (pintype "input"))
    )
    (net (code "19") (name "F3_OUT") (class "Default")
      (node (ref "J13") (pin "P$4") (pinfunction "P$4_P$4") (pintype "bidirectional"))
      (node (ref "J14") (pin "P$4") (pinfunction "P$4_P$4") (pintype "bidirectional"))
      (node (ref "J5") (pin "P$4") (pinfunction "P$4_P$4") (pintype "bidirectional"))
      (node (ref "J6") (pin "P$4") (pinfunction "P$4_P$4") (pintype "bidirectional"))
      (node (ref "U10") (pin "3") (pinfunction "C(3)_3") (pintype "input"))
      (node (ref "U15") (pin "3") (pinfunction "C(3)_3") (pintype "input"))
      (node (ref "U19") (pin "3") (pinfunction "C(3)_3") (pintype "input"))
      (node (ref "U35") (pin "3") (pinfunction "C(3)_3") (pintype "input"))
    )
    (net (code "20") (name "GND") (class "Default")
      (node (ref "C1") (pin "P$1") (pinfunction "1_P$1") (pintype "passive"))
      (node (ref "C10") (pin "P$1") (pinfunction "1_P$1") (pintype "passive"))
      (node (ref "C11") (pin "P$2") (pinfunction "2_P$2") (pintype "passive"))
      (node (ref "C13") (pin "P$1") (pinfunction "1_P$1") (pintype "passive"))
      (node (ref "C14") (pin "P$1") (pinfunction "1_P$1") (pintype "passive"))
      (node (ref "C15") (pin "2") (pinfunction "2_2") (pintype "passive"))
      (node (ref "C16") (pin "P$2") (pinfunction "2_P$2") (pintype "passive"))
      (node (ref "C2") (pin "P$1") (pinfunction "1_P$1") (pintype "passive"))
      (node (ref "C30") (pin "P$1") (pinfunction "1_P$1") (pintype "passive"))
      (node (ref "C31") (pin "P$2") (pinfunction "2_P$2") (pintype "passive"))
      (node (ref "C32") (pin "P$2") (pinfunction "2_P$2") (pintype "passive"))
      (node (ref "C33") (pin "P$2") (pinfunction "2_P$2") (pintype "passive"))
      (node (ref "C34") (pin "P$2") (pinfunction "2_P$2") (pintype "passive"))
      (node (ref "C35") (pin "P$2") (pinfunction "2_P$2") (pintype "passive"))
      (node (ref "C36") (pin "P$1") (pinfunction "1_P$1") (pintype "passive"))
      (node (ref "C37") (pin "P$1") (pinfunction "1_P$1") (pintype "passive"))
      (node (ref "C38") (pin "P$2") (pinfunction "2_P$2") (pintype "passive"))
      (node (ref "C39") (pin "P$2") (pinfunction "2_P$2") (pintype "passive"))
      (node (ref "C40") (pin "P$2") (pinfunction "2_P$2") (pintype "passive"))
      (node (ref "C41") (pin "P$2") (pinfunction "2_P$2") (pintype "passive"))
      (node (ref "C42") (pin "P$2") (pinfunction "2_P$2") (pintype "passive"))
      (node (ref "C43") (pin "2") (pinfunction "2_2") (pintype "passive"))
      (node (ref "C44") (pin "P$2") (pinfunction "2_P$2") (pintype "passive"))
      (node (ref "C45") (pin "P$2") (pinfunction "2_P$2") (pintype "passive"))
      (node (ref "C46") (pin "P$2") (pinfunction "2_P$2") (pintype "passive"))
      (node (ref "C47") (pin "P$2") (pinfunction "2_P$2") (pintype "passive"))
      (node (ref "C48") (pin "2") (pinfunction "2_2") (pintype "passive"))
      (node (ref "C49") (pin "P$2") (pinfunction "2_P$2") (pintype "passive"))
      (node (ref "C5") (pin "P$2") (pinfunction "2_P$2") (pintype "passive"))
      (node (ref "C50") (pin "P$2") (pinfunction "2_P$2") (pintype "passive"))
      (node (ref "C51") (pin "P$2") (pinfunction "2_P$2") (pintype "passive"))
      (node (ref "C52") (pin "P$2") (pinfunction "2_P$2") (pintype "passive"))
      (node (ref "C53") (pin "P$2") (pinfunction "2_P$2") (pintype "passive"))
      (node (ref "C54") (pin "P$1") (pinfunction "1_P$1") (pintype "passive"))
      (node (ref "C55") (pin "P$1") (pinfunction "1_P$1") (pintype "passive"))
      (node (ref "C56") (pin "P$1") (pinfunction "1_P$1") (pintype "passive"))
      (node (ref "C57") (pin "P$2") (pinfunction "2_P$2") (pintype "passive"))
      (node (ref "C58") (pin "P$2") (pinfunction "2_P$2") (pintype "passive"))
      (node (ref "C59") (pin "P$2") (pinfunction "2_P$2") (pintype "passive"))
      (node (ref "C60") (pin "P$2") (pinfunction "2_P$2") (pintype "passive"))
      (node (ref "C61") (pin "P$1") (pinfunction "1_P$1") (pintype "passive"))
      (node (ref "C8") (pin "P$2") (pinfunction "2_P$2") (pintype "passive"))
      (node (ref "J1") (pin "1") (pinfunction "1_1") (pintype "passive"))
      (node (ref "J1") (pin "2") (pinfunction "2_2") (pintype "passive"))
      (node (ref "J11") (pin "10") (pinfunction "10_10") (pintype "passive"))
      (node (ref "J11") (pin "6") (pinfunction "6_6") (pintype "passive"))
      (node (ref "J11") (pin "8") (pinfunction "8_8") (pintype "passive"))
      (node (ref "J16") (pin "10") (pinfunction "10_10") (pintype "passive"))
      (node (ref "J16") (pin "2") (pinfunction "2_2") (pintype "passive"))
      (node (ref "J16") (pin "4") (pinfunction "4_4") (pintype "passive"))
      (node (ref "J16") (pin "6") (pinfunction "6_6") (pintype "passive"))
      (node (ref "J16") (pin "8") (pinfunction "8_8") (pintype "passive"))
      (node (ref "J2") (pin "P$5") (pinfunction "GND_P$5") (pintype "bidirectional"))
      (node (ref "J3") (pin "GND") (pinfunction "GND_GND") (pintype "power_in"))
      (node (ref "J4") (pin "10") (pinfunction "GLO_10") (pintype "bidirectional"))
      (node (ref "J4") (pin "8") (pinfunction "P8_8") (pintype "bidirectional"))
      (node (ref "J9") (pin "6") (pinfunction "SUPPLY_VOLTAGE_GROUND_6") (pintype "power_in"))
      (node (ref "LED3") (pin "C") (pinfunction "C_C") (pintype "passive"))
      (node (ref "R16") (pin "P$1") (pinfunction "1_P$1") (pintype "passive"))
      (node (ref "R17") (pin "P$1") (pinfunction "1_P$1") (pintype "passive"))
      (node (ref "R19") (pin "P$1") (pinfunction "1_P$1") (pintype "passive"))
      (node (ref "R25") (pin "P$1") (pinfunction "1_P$1") (pintype "passive"))
      (node (ref "R7") (pin "P$1") (pinfunction "1_P$1") (pintype "passive"))
      (node (ref "U$1") (pin "P$2") (pinfunction "2_P$2") (pintype "passive"))
      (node (ref "U$10") (pin "P$2") (pinfunction "2_P$2") (pintype "passive"))
      (node (ref "U$12") (pin "P$2") (pinfunction "2_P$2") (pintype "passive"))
      (node (ref "U$13") (pin "P$2") (pinfunction "2_P$2") (pintype "passive"))
      (node (ref "U$14") (pin "P$2") (pinfunction "2_P$2") (pintype "passive"))
      (node (ref "U$15") (pin "P$2") (pinfunction "2_P$2") (pintype "passive"))
      (node (ref "U$16") (pin "P$2") (pinfunction "2_P$2") (pintype "passive"))
      (node (ref "U$17") (pin "P$2") (pinfunction "2_P$2") (pintype "passive"))
      (node (ref "U$18") (pin "P$2") (pinfunction "2_P$2") (pintype "passive"))
      (node (ref "U$3") (pin "2") (pinfunction "2_2") (pintype "bidirectional"))
      (node (ref "U$3") (pin "4") (pinfunction "4_4") (pintype "bidirectional"))
      (node (ref "U$32") (pin "P$2") (pinfunction "2_P$2") (pintype "passive"))
      (node (ref "U$33") (pin "P$2") (pinfunction "2_P$2") (pintype "passive"))
      (node (ref "U$34") (pin "P$2") (pinfunction "2_P$2") (pintype "passive"))
      (node (ref "U$35") (pin "P$2") (pinfunction "2_P$2") (pintype "passive"))
      (node (ref "U$4") (pin "P$2") (pinfunction "2_P$2") (pintype "passive"))
      (node (ref "U$5") (pin "P$2") (pinfunction "2_P$2") (pintype "passive"))
      (node (ref "U$6") (pin "P$2") (pinfunction "2_P$2") (pintype "passive"))
      (node (ref "U$8") (pin "P$2") (pinfunction "2_P$2") (pintype "passive"))
      (node (ref "U10") (pin "2") (pinfunction "E(1)_2") (pintype "output"))
      (node (ref "U12") (pin "2") (pinfunction "E(1)_2") (pintype "output"))
      (node (ref "U13") (pin "2") (pinfunction "E(1)_2") (pintype "output"))
      (node (ref "U14") (pin "2") (pinfunction "E(1)_2") (pintype "output"))
      (node (ref "U15") (pin "2") (pinfunction "E(1)_2") (pintype "output"))
      (node (ref "U16") (pin "2") (pinfunction "E(1)_2") (pintype "output"))
      (node (ref "U17") (pin "2") (pinfunction "E(1)_2") (pintype "output"))
      (node (ref "U18") (pin "2") (pinfunction "E(1)_2") (pintype "output"))
      (node (ref "U19") (pin "2") (pinfunction "E(1)_2") (pintype "output"))
      (node (ref "U2") (pin "2") (pinfunction "GND_2") (pintype "input"))
      (node (ref "U3") (pin "22") (pinfunction "GND_22") (pintype "power_in"))
      (node (ref "U3") (pin "25") (pinfunction "25_25") (pintype "passive"))
      (node (ref "U32") (pin "2") (pinfunction "E(1)_2") (pintype "output"))
      (node (ref "U33") (pin "2") (pinfunction "E(1)_2") (pintype "output"))
      (node (ref "U34") (pin "2") (pinfunction "E(1)_2") (pintype "output"))
      (node (ref "U35") (pin "2") (pinfunction "E(1)_2") (pintype "output"))
      (node (ref "U4") (pin "111") (pinfunction "VSS(IO)5_111") (pintype "bidirectional"))
      (node (ref "U4") (pin "124") (pinfunction "VSS(IO)6_124") (pintype "bidirectional"))
      (node (ref "U4") (pin "139") (pinfunction "VSS(IO)7_139") (pintype "bidirectional"))
      (node (ref "U4") (pin "150") (pinfunction "VSS(IO)8_150") (pintype "bidirectional"))
      (node (ref "U4") (pin "153") (pinfunction "VREFL_153") (pintype "bidirectional"))
      (node (ref "U4") (pin "156") (pinfunction "AVSS0_156") (pintype "bidirectional"))
      (node (ref "U4") (pin "157") (pinfunction "VREFL0_157") (pintype "bidirectional"))
      (node (ref "U4") (pin "170") (pinfunction "VSS(IO)9_170") (pintype "bidirectional"))
      (node (ref "U4") (pin "22") (pinfunction "VSS1_22") (pintype "bidirectional"))
      (node (ref "U4") (pin "28") (pinfunction "AVSS_USBHS_28") (pintype "bidirectional"))
      (node (ref "U4") (pin "29") (pinfunction "PVSS_USBHS_29") (pintype "bidirectional"))
      (node (ref "U4") (pin "30") (pinfunction "VSS2_USBHS_30") (pintype "bidirectional"))
      (node (ref "U4") (pin "33") (pinfunction "VSS1_USBHS_33") (pintype "bidirectional"))
      (node (ref "U4") (pin "35") (pinfunction "VSSIO_35") (pintype "bidirectional"))
      (node (ref "U4") (pin "45") (pinfunction "VSS_USB_45") (pintype "bidirectional"))
      (node (ref "U4") (pin "60") (pinfunction "VSS(IO)2_60") (pintype "bidirectional"))
      (node (ref "U4") (pin "63") (pinfunction "VSS(IO/DCDC)_63") (pintype "bidirectional"))
      (node (ref "U4") (pin "66") (pinfunction "VCC_DCDC(IO/DCDC)_66") (pintype "bidirectional"))
      (node (ref "U4") (pin "83") (pinfunction "VSS(IO)3_83") (pintype "bidirectional"))
      (node (ref "U4") (pin "98") (pinfunction "VSS(IO)4_98") (pintype "bidirectional"))
      (node (ref "U7") (pin "2") (pinfunction "E(1)_2") (pintype "output"))
      (node (ref "U8") (pin "2") (pinfunction "E(1)_2") (pintype "output"))
      (node (ref "U9") (pin "2") (pinfunction "E(1)_2") (pintype "output"))
      (node (ref "X4") (pin "2") (pinfunction "2_2") (pintype "bidirectional"))
      (node (ref "X4") (pin "4") (pinfunction "4_4") (pintype "bidirectional"))
    )
    (net (code "21") (name "GNDE") (class "Default")
      (node (ref "J1") (pin "10") (pinfunction "10_10") (pintype "passive"))
      (node (ref "J1") (pin "9") (pinfunction "9_9") (pintype "passive"))
      (node (ref "J2") (pin "P$6") (pinfunction "SHIELD1_P$6") (pintype "bidirectional"))
      (node (ref "J2") (pin "P$7") (pinfunction "SHIELD2_P$7") (pintype "bidirectional"))
      (node (ref "J2") (pin "P$8") (pinfunction "SHIELD3_P$8") (pintype "bidirectional"))
      (node (ref "J2") (pin "P$9") (pinfunction "SHIELD4_P$9") (pintype "bidirectional"))
      (node (ref "J3") (pin "SHLD1") (pinfunction "SHIELD_1_SHLD1") (pintype "bidirectional"))
      (node (ref "J3") (pin "SHLD2") (pinfunction "SHIELD_2_SHLD2") (pintype "bidirectional"))
      (node (ref "J4") (pin "13") (pinfunction "GNDE0_13") (pintype "bidirectional"))
      (node (ref "J4") (pin "14") (pinfunction "GNDE1_14") (pintype "bidirectional"))
      (node (ref "J9") (pin "S1") (pinfunction "SHIELD_S1") (pintype "passive"))
      (node (ref "J9") (pin "S2") (pinfunction "SHIELD_S2") (pintype "passive"))
      (node (ref "J9") (pin "S3") (pinfunction "SHIELD_S3") (pintype "passive"))
      (node (ref "J9") (pin "S4") (pinfunction "SHIELD_S4") (pintype "passive"))
    )
    (net (code "22") (name "GP4") (class "Default")
      (node (ref "U4") (pin "49") (pinfunction "P2_7_49") (pintype "bidirectional"))
    )
    (net (code "23") (name "ID") (class "Default")
      (node (ref "J2") (pin "P$4") (pinfunction "ID_P$4") (pintype "bidirectional"))
    )
    (net (code "24") (name "IIC_0_SCL") (class "Default")
      (node (ref "J7") (pin "10") (pinfunction "10_10") (pintype "passive"))
      (node (ref "R11") (pin "P$2") (pinfunction "2_P$2") (pintype "passive"))
      (node (ref "U4") (pin "1") (pinfunction "P4_0_1") (pintype "bidirectional"))
    )
    (net (code "25") (name "IIC_0_SDA") (class "Default")
      (node (ref "J7") (pin "9") (pinfunction "9_9") (pintype "passive"))
      (node (ref "R14") (pin "P$2") (pinfunction "2_P$2") (pintype "passive"))
      (node (ref "U4") (pin "2") (pinfunction "P4_1_2") (pintype "bidirectional"))
    )
    (net (code "26") (name "IIC_1_SCL") (class "Default")
      (node (ref "J10") (pin "P$5") (pinfunction "P$5_P$5") (pintype "bidirectional"))
      (node (ref "R20") (pin "P$2") (pinfunction "2_P$2") (pintype "passive"))
      (node (ref "U4") (pin "132") (pinfunction "P1_0_132") (pintype "bidirectional"))
    )
    (net (code "27") (name "IIC_1_SDA") (class "Default")
      (node (ref "J10") (pin "P$6") (pinfunction "P$6_P$6") (pintype "bidirectional"))
      (node (ref "R21") (pin "P$2") (pinfunction "2_P$2") (pintype "passive"))
      (node (ref "U4") (pin "131") (pinfunction "P1_1_131") (pintype "bidirectional"))
    )
    (net (code "28") (name "INT_AI_LS_0") (class "Default")
      (node (ref "J15") (pin "P$1") (pinfunction "P$1_P$1") (pintype "bidirectional"))
      (node (ref "U4") (pin "3") (pinfunction "P4_2_3") (pintype "bidirectional"))
    )
    (net (code "29") (name "INT_AI_LS_1") (class "Default")
      (node (ref "J15") (pin "P$2") (pinfunction "P$2_P$2") (pintype "bidirectional"))
      (node (ref "U4") (pin "43") (pinfunction "P4_8_43") (pintype "bidirectional"))
    )
    (net (code "30") (name "INT_AI_LS_2") (class "Default")
      (node (ref "J15") (pin "P$3") (pinfunction "P$3_P$3") (pintype "bidirectional"))
    )
    (net (code "31") (name "INT_AI_LS_3") (class "Default")
      (node (ref "J15") (pin "P$4") (pinfunction "P$4_P$4") (pintype "bidirectional"))
    )
    (net (code "32") (name "INT_MI_01") (class "Default")
      (node (ref "J10") (pin "P$39") (pinfunction "P$39_P$39") (pintype "bidirectional"))
      (node (ref "U4") (pin "87") (pinfunction "P3_1_87") (pintype "bidirectional"))
    )
    (net (code "33") (name "INT_MI_02") (class "Default")
      (node (ref "J10") (pin "P$40") (pinfunction "P$40_P$40") (pintype "bidirectional"))
      (node (ref "U4") (pin "86") (pinfunction "P3_2_86") (pintype "bidirectional"))
    )
    (net (code "34") (name "INT_MI_03") (class "Default")
      (node (ref "J10") (pin "P$9") (pinfunction "P$9_P$9") (pintype "bidirectional"))
      (node (ref "U4") (pin "128") (pinfunction "P1_4_128") (pintype "bidirectional"))
    )
    (net (code "35") (name "INT_MI_04") (class "Default")
      (node (ref "J10") (pin "P$10") (pinfunction "P$10_P$10") (pintype "bidirectional"))
      (node (ref "U4") (pin "127") (pinfunction "P1_5_127") (pintype "bidirectional"))
    )
    (net (code "36") (name "INT_MI_05") (class "Default")
      (node (ref "J10") (pin "P$1") (pinfunction "P$1_P$1") (pintype "bidirectional"))
    )
    (net (code "37") (name "LED1{slash}SPEED") (class "Default")
      (node (ref "J4") (pin "11") (pinfunction "YLO_11") (pintype "bidirectional"))
      (node (ref "U3") (pin "23") (pinfunction "LED0/ANEN_SPEED_23") (pintype "bidirectional"))
    )
    (net (code "38") (name "M0_DIR") (class "Default")
      (node (ref "RXS4") (pin "P$1") (pinfunction "1_P$1") (pintype "passive"))
      (node (ref "U4") (pin "39") (pinfunction "P4_12_39") (pintype "bidirectional"))
    )
    (net (code "39") (name "M0_STEP") (class "Default")
      (node (ref "RXS2") (pin "P$1") (pinfunction "1_P$1") (pintype "passive"))
      (node (ref "U4") (pin "16") (pinfunction "PB_0_16") (pintype "bidirectional"))
    )
    (net (code "40") (name "M1_DIR") (class "Default")
      (node (ref "RYS7") (pin "P$1") (pinfunction "1_P$1") (pintype "passive"))
      (node (ref "U4") (pin "40") (pinfunction "P4_11_40") (pintype "bidirectional"))
    )
    (net (code "41") (name "M1_STEP") (class "Default")
      (node (ref "RYS3") (pin "P$1") (pinfunction "1_P$1") (pintype "passive"))
      (node (ref "U4") (pin "36") (pinfunction "P4_15_36") (pintype "bidirectional"))
    )
    (net (code "42") (name "M2_DIR") (class "Default")
      (node (ref "RZS4") (pin "P$1") (pinfunction "1_P$1") (pintype "passive"))
      (node (ref "U4") (pin "41") (pinfunction "P4_10_41") (pintype "bidirectional"))
    )
    (net (code "43") (name "M2_STEP") (class "Default")
      (node (ref "RZS2") (pin "P$1") (pinfunction "1_P$1") (pintype "passive"))
      (node (ref "U4") (pin "37") (pinfunction "P4_14_37") (pintype "bidirectional"))
    )
    (net (code "44") (name "M3_DIR") (class "Default")
      (node (ref "RYS8") (pin "P$1") (pinfunction "1_P$1") (pintype "passive"))
      (node (ref "U4") (pin "42") (pinfunction "P4_9_42") (pintype "bidirectional"))
    )
    (net (code "45") (name "M3_STEP") (class "Default")
      (node (ref "RYS4") (pin "P$1") (pinfunction "1_P$1") (pintype "passive"))
      (node (ref "U4") (pin "38") (pinfunction "P4_13_38") (pintype "bidirectional"))
    )
    (net (code "46") (name "NC") (class "Default")
      (node (ref "J4") (pin "7") (pinfunction "P7_7") (pintype "bidirectional"))
    )
    (net (code "47") (name "Net-(C16-1)") (class "Default")
      (node (ref "C16") (pin "P$1") (pinfunction "1_P$1") (pintype "passive"))
      (node (ref "J2") (pin "P$1") (pinfunction "VBUS_P$1") (pintype "bidirectional"))
      (node (ref "R4") (pin "P$2") (pinfunction "2_P$2") (pintype "passive"))
      (node (ref "R7") (pin "P$2") (pinfunction "2_P$2") (pintype "passive"))
    )
    (net (code "48") (name "Net-(C31-1)") (class "Default")
      (node (ref "C31") (pin "P$1") (pinfunction "1_P$1") (pintype "passive"))
      (node (ref "U4") (pin "62") (pinfunction "VCL1_62") (pintype "bidirectional"))
    )
    (net (code "49") (name "Net-(C37-2)") (class "Default")
      (node (ref "C37") (pin "P$2") (pinfunction "2_P$2") (pintype "passive"))
      (node (ref "U4") (pin "148") (pinfunction "VCL2_148") (pintype "bidirectional"))
    )
    (net (code "50") (name "Net-(C38-1)") (class "Default")
      (node (ref "C38") (pin "P$1") (pinfunction "1_P$1") (pintype "passive"))
      (node (ref "U4") (pin "19") (pinfunction "VCLO_19") (pintype "bidirectional"))
    )
    (net (code "51") (name "Net-(C44-1)") (class "Default")
      (node (ref "C43") (pin "1") (pinfunction "1_1") (pintype "passive"))
      (node (ref "C44") (pin "P$1") (pinfunction "1_P$1") (pintype "passive"))
      (node (ref "FB2/2") (pin "2") (pinfunction "P$2_2") (pintype "bidirectional"))
      (node (ref "U3") (pin "2") (pinfunction "VDDA_3.3_2") (pintype "power_in"))
    )
    (net (code "52") (name "Net-(J2-D+)") (class "Default")
      (node (ref "J2") (pin "P$3") (pinfunction "D+_P$3") (pintype "bidirectional"))
      (node (ref "R6") (pin "P$2") (pinfunction "2_P$2") (pintype "passive"))
    )
    (net (code "53") (name "Net-(J2-D-)") (class "Default")
      (node (ref "J2") (pin "P$2") (pinfunction "D-_P$2") (pintype "bidirectional"))
      (node (ref "R5") (pin "P$2") (pinfunction "2_P$2") (pintype "passive"))
    )
    (net (code "54") (name "Net-(R13-1)") (class "Default")
      (node (ref "LED3") (pin "A") (pinfunction "A_A") (pintype "passive"))
      (node (ref "R13") (pin "P$1") (pinfunction "1_P$1") (pintype "passive"))
    )
    (net (code "55") (name "Net-(R16-2)") (class "Default")
      (node (ref "R16") (pin "P$2") (pinfunction "2_P$2") (pintype "passive"))
      (node (ref "U4") (pin "65") (pinfunction "VLO2(DCDC)_65") (pintype "bidirectional"))
    )
    (net (code "56") (name "Net-(R17-2)") (class "Default")
      (node (ref "R17") (pin "P$2") (pinfunction "2_P$2") (pintype "passive"))
      (node (ref "U4") (pin "64") (pinfunction "VLO1(DCDC)_64") (pintype "bidirectional"))
    )
    (net (code "57") (name "Net-(R19-2)") (class "Default")
      (node (ref "R19") (pin "P$2") (pinfunction "2_P$2") (pintype "passive"))
      (node (ref "U4") (pin "27") (pinfunction "USBHS_RREF_27") (pintype "bidirectional"))
    )
    (net (code "58") (name "Net-(RXS2-2)") (class "Default")
      (node (ref "RXS2") (pin "P$2") (pinfunction "2_P$2") (pintype "passive"))
      (node (ref "U$5") (pin "P$1") (pinfunction "1_P$1") (pintype "passive"))
      (node (ref "U8") (pin "1") (pinfunction "B(2)_1") (pintype "input"))
    )
    (net (code "59") (name "Net-(RXS3-2)") (class "Default")
      (node (ref "RXS3") (pin "P$2") (pinfunction "2_P$2") (pintype "passive"))
      (node (ref "U$12") (pin "P$1") (pinfunction "1_P$1") (pintype "passive"))
      (node (ref "U13") (pin "1") (pinfunction "B(2)_1") (pintype "input"))
    )
    (net (code "60") (name "Net-(RXS4-2)") (class "Default")
      (node (ref "RXS4") (pin "P$2") (pinfunction "2_P$2") (pintype "passive"))
      (node (ref "U$16") (pin "P$1") (pinfunction "1_P$1") (pintype "passive"))
      (node (ref "U17") (pin "1") (pinfunction "B(2)_1") (pintype "input"))
    )
    (net (code "61") (name "Net-(RXS8-2)") (class "Default")
      (node (ref "RXS8") (pin "P$2") (pinfunction "2_P$2") (pintype "passive"))
      (node (ref "U$33") (pin "P$1") (pinfunction "1_P$1") (pintype "passive"))
      (node (ref "U33") (pin "1") (pinfunction "B(2)_1") (pintype "input"))
    )
    (net (code "62") (name "Net-(RYS3-2)") (class "Default")
      (node (ref "RYS3") (pin "P$2") (pinfunction "2_P$2") (pintype "passive"))
      (node (ref "U$6") (pin "P$1") (pinfunction "1_P$1") (pintype "passive"))
      (node (ref "U9") (pin "1") (pinfunction "B(2)_1") (pintype "input"))
    )
    (net (code "63") (name "Net-(RYS4-2)") (class "Default")
      (node (ref "RYS4") (pin "P$2") (pinfunction "2_P$2") (pintype "passive"))
      (node (ref "U$8") (pin "P$1") (pinfunction "1_P$1") (pintype "passive"))
      (node (ref "U10") (pin "1") (pinfunction "B(2)_1") (pintype "input"))
    )
    (net (code "64") (name "Net-(RYS5-2)") (class "Default")
      (node (ref "RYS5") (pin "P$2") (pinfunction "2_P$2") (pintype "passive"))
      (node (ref "U$13") (pin "P$1") (pinfunction "1_P$1") (pintype "passive"))
      (node (ref "U14") (pin "1") (pinfunction "B(2)_1") (pintype "input"))
    )
    (net (code "65") (name "Net-(RYS6-2)") (class "Default")
      (node (ref "RYS6") (pin "P$2") (pinfunction "2_P$2") (pintype "passive"))
      (node (ref "U$14") (pin "P$1") (pinfunction "1_P$1") (pintype "passive"))
      (node (ref "U15") (pin "1") (pinfunction "B(2)_1") (pintype "input"))
    )
    (net (code "66") (name "Net-(RYS7-2)") (class "Default")
      (node (ref "RYS7") (pin "P$2") (pinfunction "2_P$2") (pintype "passive"))
      (node (ref "U$17") (pin "P$1") (pinfunction "1_P$1") (pintype "passive"))
      (node (ref "U18") (pin "1") (pinfunction "B(2)_1") (pintype "input"))
    )
    (net (code "67") (name "Net-(RYS8-2)") (class "Default")
      (node (ref "RYS8") (pin "P$2") (pinfunction "2_P$2") (pintype "passive"))
      (node (ref "U$18") (pin "P$1") (pinfunction "1_P$1") (pintype "passive"))
      (node (ref "U19") (pin "1") (pinfunction "B(2)_1") (pintype "input"))
    )
    (net (code "68") (name "Net-(RYS15-2)") (class "Default")
      (node (ref "RYS15") (pin "P$2") (pinfunction "2_P$2") (pintype "passive"))
      (node (ref "U$34") (pin "P$1") (pinfunction "1_P$1") (pintype "passive"))
      (node (ref "U34") (pin "1") (pinfunction "B(2)_1") (pintype "input"))
    )
    (net (code "69") (name "Net-(RYS16-2)") (class "Default")
      (node (ref "RYS16") (pin "P$2") (pinfunction "2_P$2") (pintype "passive"))
      (node (ref "U$35") (pin "P$1") (pinfunction "1_P$1") (pintype "passive"))
      (node (ref "U35") (pin "1") (pinfunction "B(2)_1") (pintype "input"))
    )
    (net (code "70") (name "Net-(RZS2-2)") (class "Default")
      (node (ref "RZS2") (pin "P$2") (pinfunction "2_P$2") (pintype "passive"))
      (node (ref "U$1") (pin "P$1") (pinfunction "1_P$1") (pintype "passive"))
      (node (ref "U7") (pin "1") (pinfunction "B(2)_1") (pintype "input"))
    )
    (net (code "71") (name "Net-(RZS3-2)") (class "Default")
      (node (ref "RZS3") (pin "P$2") (pinfunction "2_P$2") (pintype "passive"))
      (node (ref "U$10") (pin "P$1") (pinfunction "1_P$1") (pintype "passive"))
      (node (ref "U12") (pin "1") (pinfunction "B(2)_1") (pintype "input"))
    )
    (net (code "72") (name "Net-(RZS4-2)") (class "Default")
      (node (ref "RZS4") (pin "P$2") (pinfunction "2_P$2") (pintype "passive"))
      (node (ref "U$15") (pin "P$1") (pinfunction "1_P$1") (pintype "passive"))
      (node (ref "U16") (pin "1") (pinfunction "B(2)_1") (pintype "input"))
    )
    (net (code "73") (name "Net-(RZS8-2)") (class "Default")
      (node (ref "RZS8") (pin "P$2") (pinfunction "2_P$2") (pintype "passive"))
      (node (ref "U$32") (pin "P$1") (pinfunction "1_P$1") (pintype "passive"))
      (node (ref "U32") (pin "1") (pinfunction "B(2)_1") (pintype "input"))
    )
    (net (code "74") (name "P0_00") (class "Default")
      (node (ref "J7") (pin "3") (pinfunction "3_3") (pintype "passive"))
      (node (ref "U4") (pin "169") (pinfunction "P0_0/AN0\\00_169") (pintype "bidirectional"))
    )
    (net (code "75") (name "P0_01") (class "Default")
      (node (ref "J7") (pin "4") (pinfunction "4_4") (pintype "passive"))
      (node (ref "U4") (pin "168") (pinfunction "P0_1/AN001_168") (pintype "bidirectional"))
    )
    (net (code "76") (name "P0_02") (class "Default")
      (node (ref "J7") (pin "1") (pinfunction "1_1") (pintype "passive"))
      (node (ref "U4") (pin "167") (pinfunction "P0_2/AN002_167") (pintype "bidirectional"))
    )
    (net (code "77") (name "P0_03") (class "Default")
      (node (ref "J7") (pin "2") (pinfunction "2_2") (pintype "passive"))
      (node (ref "U4") (pin "166") (pinfunction "P0_3/PGAVSS000_166") (pintype "bidirectional"))
    )
    (net (code "78") (name "P0_04") (class "Default")
      (node (ref "J8") (pin "9") (pinfunction "9_9") (pintype "passive"))
      (node (ref "U4") (pin "165") (pinfunction "P0_4/AN100_165") (pintype "bidirectional"))
    )
    (net (code "79") (name "P0_05") (class "Default")
      (node (ref "J8") (pin "10") (pinfunction "10_10") (pintype "passive"))
      (node (ref "U4") (pin "164") (pinfunction "P0_5/AN101_164") (pintype "bidirectional"))
    )
    (net (code "80") (name "P0_06") (class "Default")
      (node (ref "J8") (pin "7") (pinfunction "7_7") (pintype "passive"))
      (node (ref "U4") (pin "163") (pinfunction "P0_6/AN102_163") (pintype "bidirectional"))
    )
    (net (code "81") (name "P0_07") (class "Default")
      (node (ref "J8") (pin "8") (pinfunction "8_8") (pintype "passive"))
      (node (ref "U4") (pin "162") (pinfunction "P0_7/PGVSS100_162") (pintype "bidirectional"))
    )
    (net (code "82") (name "P0_08") (class "Default")
      (node (ref "J8") (pin "5") (pinfunction "5_5") (pintype "passive"))
      (node (ref "U4") (pin "161") (pinfunction "P0_8/AN003_161") (pintype "bidirectional"))
    )
    (net (code "83") (name "P0_09") (class "Default")
      (node (ref "J8") (pin "6") (pinfunction "6_6") (pintype "passive"))
      (node (ref "U4") (pin "160") (pinfunction "P0_9/AN004_160") (pintype "bidirectional"))
    )
    (net (code "84") (name "P0_14") (class "Default")
      (node (ref "J8") (pin "3") (pinfunction "3_3") (pintype "passive"))
      (node (ref "U4") (pin "152") (pinfunction "P0_14/DA0/AN005/AN105_152") (pintype "bidirectional"))
    )
    (net (code "85") (name "P0_15") (class "Default")
      (node (ref "J8") (pin "4") (pinfunction "4_4") (pintype "passive"))
      (node (ref "U4") (pin "151") (pinfunction "P0_15/DA1/AN006/AN106_151") (pintype "bidirectional"))
    )
    (net (code "86") (name "P1_02") (class "Default")
      (node (ref "J10") (pin "P$7") (pinfunction "P$7_P$7") (pintype "bidirectional"))
      (node (ref "U4") (pin "130") (pinfunction "P1_2_130") (pintype "bidirectional"))
    )
    (net (code "87") (name "P1_03") (class "Default")
      (node (ref "J10") (pin "P$8") (pinfunction "P$8_P$8") (pintype "bidirectional"))
      (node (ref "U4") (pin "129") (pinfunction "P1_3_129") (pintype "bidirectional"))
    )
    (net (code "88") (name "P1_06") (class "Default")
      (node (ref "J10") (pin "P$11") (pinfunction "P$11_P$11") (pintype "bidirectional"))
      (node (ref "U4") (pin "126") (pinfunction "P1_6_126") (pintype "bidirectional"))
    )
    (net (code "89") (name "P1_07") (class "Default")
      (node (ref "J10") (pin "P$12") (pinfunction "P$12_P$12") (pintype "bidirectional"))
      (node (ref "U4") (pin "125") (pinfunction "P1_7_125") (pintype "bidirectional"))
    )
    (net (code "90") (name "P1_11") (class "Default")
      (node (ref "J10") (pin "P$38") (pinfunction "P$38_P$38") (pintype "bidirectional"))
      (node (ref "U4") (pin "92") (pinfunction "P1_11_92") (pintype "bidirectional"))
    )
    (net (code "91") (name "P1_12") (class "Default")
      (node (ref "J10") (pin "P$37") (pinfunction "P$37_P$37") (pintype "bidirectional"))
      (node (ref "U4") (pin "93") (pinfunction "P1_12_93") (pintype "bidirectional"))
    )
    (net (code "92") (name "P1_13") (class "Default")
      (node (ref "J10") (pin "P$36") (pinfunction "P$36_P$36") (pintype "bidirectional"))
      (node (ref "U4") (pin "94") (pinfunction "P1_13_94") (pintype "bidirectional"))
    )
    (net (code "93") (name "P1_14") (class "Default")
      (node (ref "J10") (pin "P$35") (pinfunction "P$35_P$35") (pintype "bidirectional"))
      (node (ref "U4") (pin "95") (pinfunction "P1_14_95") (pintype "bidirectional"))
    )
    (net (code "94") (name "P1_15") (class "Default")
      (node (ref "J10") (pin "P$34") (pinfunction "P$34_P$34") (pintype "bidirectional"))
      (node (ref "U4") (pin "96") (pinfunction "P1_15_96") (pintype "bidirectional"))
    )
    (net (code "95") (name "P2_00") (class "Default")
      (node (ref "J16") (pin "3") (pinfunction "3_3") (pintype "passive"))
      (node (ref "R3") (pin "P$2") (pinfunction "2_P$2") (pintype "passive"))
      (node (ref "U4") (pin "69") (pinfunction "P2_0(INPUT_ONLY)_69") (pintype "bidirectional"))
    )
    (net (code "96") (name "P2_01") (class "Default")
      (node (ref "J16") (pin "1") (pinfunction "1_1") (pintype "passive"))
      (node (ref "R2") (pin "P$2") (pinfunction "2_P$2") (pintype "passive"))
      (node (ref "U4") (pin "68") (pinfunction "P2_1/MD_68") (pintype "bidirectional"))
    )
    (net (code "97") (name "P3_03") (class "Default")
      (node (ref "J12") (pin "1") (pinfunction "1_1") (pintype "passive"))
      (node (ref "U4") (pin "85") (pinfunction "P3_3_85") (pintype "bidirectional"))
    )
    (net (code "98") (name "P3_04") (class "Default")
      (node (ref "J12") (pin "2") (pinfunction "2_2") (pintype "passive"))
      (node (ref "U4") (pin "82") (pinfunction "P3_4_82") (pintype "bidirectional"))
    )
    (net (code "99") (name "P3_05") (class "Default")
      (node (ref "J12") (pin "3") (pinfunction "3_3") (pintype "passive"))
      (node (ref "U4") (pin "81") (pinfunction "P3_5_81") (pintype "bidirectional"))
    )
    (net (code "100") (name "P3_06") (class "Default")
      (node (ref "J12") (pin "4") (pinfunction "4_4") (pintype "passive"))
      (node (ref "U4") (pin "80") (pinfunction "P3_6_80") (pintype "bidirectional"))
    )
    (net (code "101") (name "P3_07") (class "Default")
      (node (ref "J12") (pin "5") (pinfunction "5_5") (pintype "passive"))
      (node (ref "U4") (pin "79") (pinfunction "P3_7_79") (pintype "bidirectional"))
    )
    (net (code "102") (name "P3_09") (class "Default")
      (node (ref "J12") (pin "6") (pinfunction "6_6") (pintype "passive"))
      (node (ref "U4") (pin "77") (pinfunction "P3_9_77") (pintype "bidirectional"))
    )
    (net (code "103") (name "P3_10") (class "Default")
      (node (ref "J12") (pin "7") (pinfunction "7_7") (pintype "passive"))
      (node (ref "U4") (pin "76") (pinfunction "P3_10_76") (pintype "bidirectional"))
    )
    (net (code "104") (name "P3_11") (class "Default")
      (node (ref "J12") (pin "8") (pinfunction "8_8") (pintype "passive"))
      (node (ref "U4") (pin "75") (pinfunction "P3_11_75") (pintype "bidirectional"))
    )
    (net (code "105") (name "P3_12") (class "Default")
      (node (ref "J12") (pin "9") (pinfunction "9_9") (pintype "passive"))
      (node (ref "U4") (pin "74") (pinfunction "P3_12_74") (pintype "bidirectional"))
    )
    (net (code "106") (name "P5_11") (class "Default")
      (node (ref "J7") (pin "7") (pinfunction "7_7") (pintype "passive"))
      (node (ref "U4") (pin "176") (pinfunction "P5_11_176") (pintype "bidirectional"))
    )
    (net (code "107") (name "P5_12") (class "Default")
      (node (ref "J7") (pin "8") (pinfunction "8_8") (pintype "passive"))
      (node (ref "U4") (pin "175") (pinfunction "P5_12_175") (pintype "bidirectional"))
    )
    (net (code "108") (name "P5_13") (class "Default")
      (node (ref "J7") (pin "5") (pinfunction "5_5") (pintype "passive"))
      (node (ref "U4") (pin "174") (pinfunction "P5_13_174") (pintype "bidirectional"))
    )
    (net (code "109") (name "P6_00") (class "Default")
      (node (ref "J10") (pin "P$13") (pinfunction "P$13_P$13") (pintype "bidirectional"))
      (node (ref "U4") (pin "122") (pinfunction "P6_0_122") (pintype "bidirectional"))
    )
    (net (code "110") (name "P6_01") (class "Default")
      (node (ref "J10") (pin "P$14") (pinfunction "P$14_P$14") (pintype "bidirectional"))
      (node (ref "U4") (pin "121") (pinfunction "P6_1_121") (pintype "bidirectional"))
    )
    (net (code "111") (name "P6_02") (class "Default")
      (node (ref "J10") (pin "P$15") (pinfunction "P$15_P$15") (pintype "bidirectional"))
      (node (ref "U4") (pin "120") (pinfunction "P6_2_120") (pintype "bidirectional"))
    )
    (net (code "112") (name "P6_03") (class "Default")
      (node (ref "J10") (pin "P$16") (pinfunction "P$16_P$16") (pintype "bidirectional"))
      (node (ref "U4") (pin "119") (pinfunction "P6_3_119") (pintype "bidirectional"))
    )
    (net (code "113") (name "P6_04") (class "Default")
      (node (ref "J10") (pin "P$17") (pinfunction "P$17_P$17") (pintype "bidirectional"))
      (node (ref "U4") (pin "118") (pinfunction "P6_4_118") (pintype "bidirectional"))
    )
    (net (code "114") (name "P6_05") (class "Default")
      (node (ref "J10") (pin "P$18") (pinfunction "P$18_P$18") (pintype "bidirectional"))
      (node (ref "U4") (pin "117") (pinfunction "P6_5_117") (pintype "bidirectional"))
    )
    (net (code "115") (name "P6_06") (class "Default")
      (node (ref "J10") (pin "P$19") (pinfunction "P$19_P$19") (pintype "bidirectional"))
      (node (ref "U4") (pin "116") (pinfunction "P6_6_116") (pintype "bidirectional"))
    )
    (net (code "116") (name "P6_07") (class "Default")
      (node (ref "J10") (pin "P$20") (pinfunction "P$20_P$20") (pintype "bidirectional"))
      (node (ref "U4") (pin "115") (pinfunction "P6_7_115") (pintype "bidirectional"))
    )
    (net (code "117") (name "P6_08") (class "Default")
      (node (ref "J10") (pin "P$33") (pinfunction "P$33_P$33") (pintype "bidirectional"))
      (node (ref "U4") (pin "99") (pinfunction "P6_8_99") (pintype "bidirectional"))
    )
    (net (code "118") (name "P6_09") (class "Default")
      (node (ref "J10") (pin "P$32") (pinfunction "P$32_P$32") (pintype "bidirectional"))
      (node (ref "U4") (pin "100") (pinfunction "P6_9_100") (pintype "bidirectional"))
    )
    (net (code "119") (name "P6_10") (class "Default")
      (node (ref "J10") (pin "P$31") (pinfunction "P$31_P$31") (pintype "bidirectional"))
      (node (ref "U4") (pin "101") (pinfunction "P6_10_101") (pintype "bidirectional"))
    )
    (net (code "120") (name "P6_11") (class "Default")
      (node (ref "J10") (pin "P$30") (pinfunction "P$30_P$30") (pintype "bidirectional"))
      (node (ref "U4") (pin "102") (pinfunction "P6_11_102") (pintype "bidirectional"))
    )
    (net (code "121") (name "P6_12") (class "Default")
      (node (ref "J10") (pin "P$29") (pinfunction "P$29_P$29") (pintype "bidirectional"))
      (node (ref "U4") (pin "103") (pinfunction "P6_12_103") (pintype "bidirectional"))
    )
    (net (code "122") (name "P6_13") (class "Default")
      (node (ref "J10") (pin "P$28") (pinfunction "P$28_P$28") (pintype "bidirectional"))
      (node (ref "U4") (pin "104") (pinfunction "P6_13_104") (pintype "bidirectional"))
    )
    (net (code "123") (name "P6_14") (class "Default")
      (node (ref "J10") (pin "P$27") (pinfunction "P$27_P$27") (pintype "bidirectional"))
      (node (ref "U4") (pin "105") (pinfunction "P6_14_105") (pintype "bidirectional"))
    )
    (net (code "124") (name "P6_15") (class "Default")
      (node (ref "J10") (pin "P$26") (pinfunction "P$26_P$26") (pintype "bidirectional"))
      (node (ref "U4") (pin "106") (pinfunction "P6_15_106") (pintype "bidirectional"))
    )
    (net (code "125") (name "P7_06") (class "Default")
      (node (ref "U4") (pin "14") (pinfunction "P7_6_14") (pintype "bidirectional"))
    )
    (net (code "126") (name "P7_07") (class "Default")
      (node (ref "U4") (pin "15") (pinfunction "P7_7_15") (pintype "bidirectional"))
    )
    (net (code "127") (name "P8_00") (class "Default")
      (node (ref "J10") (pin "P$4") (pinfunction "P$4_P$4") (pintype "bidirectional"))
      (node (ref "U4") (pin "133") (pinfunction "P8_0_133") (pintype "bidirectional"))
    )
    (net (code "128") (name "P8_01") (class "Default")
      (node (ref "J10") (pin "P$3") (pinfunction "P$3_P$3") (pintype "bidirectional"))
      (node (ref "U4") (pin "134") (pinfunction "P8_1_134") (pintype "bidirectional"))
    )
    (net (code "129") (name "P8_02") (class "Default")
      (node (ref "J10") (pin "P$2") (pinfunction "P$2_P$2") (pintype "bidirectional"))
      (node (ref "U4") (pin "135") (pinfunction "P8_2_135") (pintype "bidirectional"))
    )
    (net (code "130") (name "P8_03") (class "Default")
      (node (ref "J8") (pin "2") (pinfunction "2_2") (pintype "passive"))
      (node (ref "U4") (pin "136") (pinfunction "P8_3_136") (pintype "bidirectional"))
    )
    (net (code "131") (name "P8_04") (class "Default")
      (node (ref "J8") (pin "1") (pinfunction "1_1") (pintype "passive"))
      (node (ref "U4") (pin "137") (pinfunction "P8_4_137") (pintype "bidirectional"))
    )
    (net (code "132") (name "P8_05") (class "Default")
      (node (ref "J7") (pin "6") (pinfunction "6_6") (pintype "passive"))
      (node (ref "U4") (pin "173") (pinfunction "P8_5_173") (pintype "bidirectional"))
    )
    (net (code "133") (name "P9_05") (class "Default")
      (node (ref "J12") (pin "10") (pinfunction "10_10") (pintype "passive"))
      (node (ref "U4") (pin "73") (pinfunction "P9_5_73") (pintype "bidirectional"))
    )
    (net (code "134") (name "P9_06") (class "Default")
      (node (ref "J16") (pin "9") (pinfunction "9_9") (pintype "passive"))
      (node (ref "R10") (pin "P$2") (pinfunction "2_P$2") (pintype "passive"))
      (node (ref "U4") (pin "72") (pinfunction "P9_6_72") (pintype "bidirectional"))
    )
    (net (code "135") (name "P9_07") (class "Default")
      (node (ref "J16") (pin "7") (pinfunction "7_7") (pintype "passive"))
      (node (ref "R9") (pin "P$2") (pinfunction "2_P$2") (pintype "passive"))
      (node (ref "U4") (pin "71") (pinfunction "P9_7_71") (pintype "bidirectional"))
    )
    (net (code "136") (name "P9_08") (class "Default")
      (node (ref "J16") (pin "5") (pinfunction "5_5") (pintype "passive"))
      (node (ref "R8") (pin "P$2") (pinfunction "2_P$2") (pintype "passive"))
      (node (ref "U4") (pin "70") (pinfunction "P9_8_70") (pintype "bidirectional"))
    )
    (net (code "137") (name "PA_00") (class "Default")
      (node (ref "J10") (pin "P$21") (pinfunction "P$21_P$21") (pintype "bidirectional"))
      (node (ref "U4") (pin "114") (pinfunction "PA_0_114") (pintype "bidirectional"))
    )
    (net (code "138") (name "PA_01") (class "Default")
      (node (ref "J10") (pin "P$22") (pinfunction "P$22_P$22") (pintype "bidirectional"))
      (node (ref "U4") (pin "113") (pinfunction "PA_1_113") (pintype "bidirectional"))
    )
    (net (code "139") (name "PA_08") (class "Default")
      (node (ref "J10") (pin "P$25") (pinfunction "P$25_P$25") (pintype "bidirectional"))
      (node (ref "U4") (pin "107") (pinfunction "PA_8_107") (pintype "bidirectional"))
    )
    (net (code "140") (name "PA_09") (class "Default")
      (node (ref "J10") (pin "P$24") (pinfunction "P$24_P$24") (pintype "bidirectional"))
      (node (ref "U4") (pin "108") (pinfunction "PA_9_108") (pintype "bidirectional"))
    )
    (net (code "141") (name "PA_10") (class "Default")
      (node (ref "J10") (pin "P$23") (pinfunction "P$23_P$23") (pintype "bidirectional"))
      (node (ref "U4") (pin "109") (pinfunction "PA_10_109") (pintype "bidirectional"))
    )
    (net (code "142") (name "R51") (class "Default")
      (node (ref "J4") (pin "12") (pinfunction "YHI_12") (pintype "bidirectional"))
      (node (ref "R23") (pin "P$1") (pinfunction "1_P$1") (pintype "passive"))
    )
    (net (code "143") (name "R52") (class "Default")
      (node (ref "J4") (pin "9") (pinfunction "GHI_9") (pintype "bidirectional"))
      (node (ref "R24") (pin "P$1") (pinfunction "1_P$1") (pintype "passive"))
    )
    (net (code "144") (name "RELAY_0") (class "Default")
      (node (ref "RYS6") (pin "P$1") (pinfunction "1_P$1") (pintype "passive"))
      (node (ref "U4") (pin "59") (pinfunction "P9_1_59") (pintype "bidirectional"))
    )
    (net (code "145") (name "RELAY_1") (class "Default")
      (node (ref "RZS3") (pin "P$1") (pinfunction "1_P$1") (pintype "passive"))
      (node (ref "U4") (pin "58") (pinfunction "P9_0_58") (pintype "bidirectional"))
    )
    (net (code "146") (name "RELAY_2") (class "Default")
      (node (ref "RYS5") (pin "P$1") (pinfunction "1_P$1") (pintype "passive"))
      (node (ref "U4") (pin "57") (pinfunction "P3_15_57") (pintype "bidirectional"))
    )
    (net (code "147") (name "RELAY_3") (class "Default")
      (node (ref "RXS3") (pin "P$1") (pinfunction "1_P$1") (pintype "passive"))
      (node (ref "U4") (pin "56") (pinfunction "P3_14_56") (pintype "bidirectional"))
    )
    (net (code "148") (name "RELAY_4") (class "Default")
      (node (ref "RYS16") (pin "P$1") (pinfunction "1_P$1") (pintype "passive"))
    )
    (net (code "149") (name "RELAY_5") (class "Default")
      (node (ref "RZS8") (pin "P$1") (pinfunction "1_P$1") (pintype "passive"))
    )
    (net (code "150") (name "RELAY_6") (class "Default")
      (node (ref "RYS15") (pin "P$1") (pinfunction "1_P$1") (pintype "passive"))
      (node (ref "U4") (pin "51") (pinfunction "P2_5_51") (pintype "bidirectional"))
    )
    (net (code "151") (name "RELAY_7") (class "Default")
      (node (ref "RXS8") (pin "P$1") (pinfunction "1_P$1") (pintype "passive"))
      (node (ref "U4") (pin "50") (pinfunction "P2_6_50") (pintype "bidirectional"))
    )
    (net (code "152") (name "RESET") (class "Default")
      (node (ref "C57") (pin "P$1") (pinfunction "1_P$1") (pintype "passive"))
      (node (ref "J11") (pin "9") (pinfunction "9_9") (pintype "passive"))
      (node (ref "R18") (pin "P$1") (pinfunction "1_P$1") (pintype "passive"))
      (node (ref "U4") (pin "67") (pinfunction "RES#_67") (pintype "bidirectional"))
    )
    (net (code "153") (name "REXT") (class "Default")
      (node (ref "C47") (pin "P$1") (pinfunction "1_P$1") (pintype "passive"))
      (node (ref "R25") (pin "P$2") (pinfunction "2_P$2") (pintype "passive"))
      (node (ref "U3") (pin "9") (pinfunction "REXT_9") (pintype "input"))
    )
    (net (code "154") (name "RXD0") (class "Default")
      (node (ref "R31") (pin "P$2") (pinfunction "2_P$2") (pintype "passive"))
      (node (ref "U3") (pin "13") (pinfunction "RXD0_13") (pintype "bidirectional"))
    )
    (net (code "155") (name "RXD1") (class "Default")
      (node (ref "R30") (pin "P$2") (pinfunction "2_P$2") (pintype "passive"))
      (node (ref "U3") (pin "12") (pinfunction "RXD1_12") (pintype "bidirectional"))
    )
    (net (code "156") (name "RXER") (class "Default")
      (node (ref "R32") (pin "P$2") (pinfunction "2_P$2") (pintype "passive"))
      (node (ref "U3") (pin "17") (pinfunction "RXER_17") (pintype "bidirectional"))
    )
    (net (code "157") (name "RXM") (class "Default")
      (node (ref "J4") (pin "6") (pinfunction "RD-_6") (pintype "bidirectional"))
      (node (ref "U3") (pin "3") (pinfunction "RXM_3") (pintype "bidirectional"))
    )
    (net (code "158") (name "RXP") (class "Default")
      (node (ref "J4") (pin "3") (pinfunction "RD+_3") (pintype "bidirectional"))
      (node (ref "U3") (pin "4") (pinfunction "RXP_4") (pintype "bidirectional"))
    )
    (net (code "159") (name "SD1_CD") (class "Default")
      (node (ref "J9") (pin "10") (pinfunction "CD_SWITCH2_10") (pintype "bidirectional"))
      (node (ref "U4") (pin "146") (pinfunction "P5_6/AN019_146") (pintype "bidirectional"))
    )
    (net (code "160") (name "SD1_CLK") (class "Default")
      (node (ref "J9") (pin "5") (pinfunction "CLOCK_5") (pintype "bidirectional"))
      (node (ref "U4") (pin "140") (pinfunction "P5_0/AN016_140") (pintype "bidirectional"))
    )
    (net (code "161") (name "SD1_CMD") (class "Default")
      (node (ref "J9") (pin "3") (pinfunction "COMMAND/RESPONSE_3") (pintype "bidirectional"))
      (node (ref "U4") (pin "141") (pinfunction "P5_1/AN116_141") (pintype "bidirectional"))
    )
    (net (code "162") (name "SD1_DAT0") (class "Default")
      (node (ref "J9") (pin "7") (pinfunction "DATA_LINE[BIT_0]_7") (pintype "bidirectional"))
      (node (ref "U4") (pin "142") (pinfunction "P5_2/AN017_142") (pintype "bidirectional"))
    )
    (net (code "163") (name "SD1_DAT1") (class "Default")
      (node (ref "J9") (pin "8") (pinfunction "DATA_LINE[BIT_1]_8") (pintype "bidirectional"))
      (node (ref "U4") (pin "143") (pinfunction "P5_3/AN117_143") (pintype "bidirectional"))
    )
    (net (code "164") (name "SD1_DAT2") (class "Default")
      (node (ref "J9") (pin "1") (pinfunction "DATA_LINE[BIT_2]_1") (pintype "bidirectional"))
      (node (ref "U4") (pin "144") (pinfunction "P5_4/AN018_144") (pintype "bidirectional"))
    )
    (net (code "165") (name "SD1_DAT3") (class "Default")
      (node (ref "J9") (pin "2") (pinfunction "CARD_DETECT/DATA_LINE[BIT_3]_2") (pintype "bidirectional"))
      (node (ref "U4") (pin "145") (pinfunction "P5_5/AN118_145") (pintype "bidirectional"))
    )
    (net (code "166") (name "SD1_WP") (class "Default")
      (node (ref "J9") (pin "9") (pinfunction "CD_SWITCH1_9") (pintype "bidirectional"))
      (node (ref "U4") (pin "147") (pinfunction "P5_7/AN119_147") (pintype "bidirectional"))
    )
    (net (code "167") (name "SPI_1_CLK") (class "Default")
      (node (ref "U4") (pin "52") (pinfunction "P2_4_52") (pintype "bidirectional"))
    )
    (net (code "168") (name "SPI_1_MISO") (class "Default")
      (node (ref "U4") (pin "54") (pinfunction "P2_2_54") (pintype "bidirectional"))
    )
    (net (code "169") (name "SPI_1_MOSI") (class "Default")
      (node (ref "U4") (pin "53") (pinfunction "P2_3_53") (pintype "bidirectional"))
    )
    (net (code "170") (name "SPI_1_SS_1") (class "Default")
      (node (ref "U4") (pin "55") (pinfunction "P3_13_55") (pintype "bidirectional"))
    )
    (net (code "171") (name "TCK") (class "Default")
      (node (ref "J11") (pin "7") (pinfunction "7_7") (pintype "passive"))
      (node (ref "U4") (pin "88") (pinfunction "P3_0_88") (pintype "bidirectional"))
    )
    (net (code "172") (name "TDI") (class "Default")
      (node (ref "J11") (pin "1") (pinfunction "1_1") (pintype "passive"))
      (node (ref "U4") (pin "91") (pinfunction "P1_10_91") (pintype "bidirectional"))
    )
    (net (code "173") (name "TDO") (class "Default")
      (node (ref "J11") (pin "3") (pinfunction "3_3") (pintype "passive"))
      (node (ref "U4") (pin "90") (pinfunction "P1_9_90") (pintype "bidirectional"))
    )
    (net (code "174") (name "TMS") (class "Default")
      (node (ref "J11") (pin "5") (pinfunction "5_5") (pintype "passive"))
      (node (ref "U4") (pin "89") (pinfunction "P1_8_89") (pintype "bidirectional"))
    )
    (net (code "175") (name "TXM") (class "Default")
      (node (ref "J4") (pin "2") (pinfunction "TD-_2") (pintype "bidirectional"))
      (node (ref "U3") (pin "5") (pinfunction "TXM_5") (pintype "bidirectional"))
    )
    (net (code "176") (name "TXP") (class "Default")
      (node (ref "J4") (pin "1") (pinfunction "TD+_1") (pintype "bidirectional"))
      (node (ref "U3") (pin "6") (pinfunction "TXP_6") (pintype "bidirectional"))
    )
    (net (code "177") (name "USBHS_FAULT") (class "Default")
      (node (ref "R12") (pin "P$1") (pinfunction "1_P$1") (pintype "passive"))
      (node (ref "U2") (pin "3") (pinfunction "FLG_3") (pintype "input"))
      (node (ref "U4") (pin "78") (pinfunction "P3_8_78") (pintype "bidirectional"))
    )
    (net (code "178") (name "USBHS_N") (class "Default")
      (node (ref "J3") (pin "D-") (pinfunction "D-_D-") (pintype "bidirectional"))
      (node (ref "U4") (pin "31") (pinfunction "USBHS_DM_31") (pintype "bidirectional"))
    )
    (net (code "179") (name "USBHS_P") (class "Default")
      (node (ref "J3") (pin "D+") (pinfunction "D+_D+") (pintype "bidirectional"))
      (node (ref "U4") (pin "32") (pinfunction "USBHS_DP_32") (pintype "bidirectional"))
    )
    (net (code "180") (name "USBHS_VBUS") (class "Default")
      (node (ref "C11") (pin "P$1") (pinfunction "1_P$1") (pintype "passive"))
      (node (ref "C15") (pin "1") (pinfunction "1_1") (pintype "passive"))
      (node (ref "J3") (pin "VBUS") (pinfunction "VBUS_VBUS") (pintype "power_in"))
      (node (ref "U2") (pin "5") (pinfunction "OUT_5") (pintype "input"))
      (node (ref "U4") (pin "17") (pinfunction "PB_1_17") (pintype "bidirectional"))
    )
    (net (code "181") (name "USBHS_VBUSEN") (class "Default")
      (node (ref "R1") (pin "P$1") (pinfunction "1_P$1") (pintype "passive"))
      (node (ref "U2") (pin "1") (pinfunction "EN_1") (pintype "input"))
    )
    (net (code "182") (name "USB_N") (class "Default")
      (node (ref "R5") (pin "P$1") (pinfunction "1_P$1") (pintype "passive"))
      (node (ref "U4") (pin "46") (pinfunction "USB_DM_46") (pintype "bidirectional"))
    )
    (net (code "183") (name "USB_P") (class "Default")
      (node (ref "R6") (pin "P$1") (pinfunction "1_P$1") (pintype "passive"))
      (node (ref "U4") (pin "47") (pinfunction "USB_DP_47") (pintype "bidirectional"))
    )
    (net (code "184") (name "USB_VBUS_B") (class "Default")
      (node (ref "R4") (pin "P$1") (pinfunction "1_P$1") (pintype "passive"))
      (node (ref "U4") (pin "44") (pinfunction "P4_7_44") (pintype "bidirectional"))
    )
    (net (code "185") (name "VCL_F(FLASH)") (class "Default")
      (node (ref "C36") (pin "P$2") (pinfunction "2_P$2") (pintype "passive"))
      (node (ref "U4") (pin "112") (pinfunction "VCL_F(FLASH)_112") (pintype "bidirectional"))
    )
    (net (code "186") (name "VDD") (class "Default")
      (node (ref "C1") (pin "P$2") (pinfunction "2_P$2") (pintype "passive"))
      (node (ref "C10") (pin "P$2") (pinfunction "2_P$2") (pintype "passive"))
      (node (ref "C13") (pin "P$2") (pinfunction "2_P$2") (pintype "passive"))
      (node (ref "C14") (pin "P$2") (pinfunction "2_P$2") (pintype "passive"))
      (node (ref "C2") (pin "P$2") (pinfunction "2_P$2") (pintype "passive"))
      (node (ref "C30") (pin "P$2") (pinfunction "2_P$2") (pintype "passive"))
      (node (ref "C32") (pin "P$1") (pinfunction "1_P$1") (pintype "passive"))
      (node (ref "C33") (pin "P$1") (pinfunction "1_P$1") (pintype "passive"))
      (node (ref "C34") (pin "P$1") (pinfunction "1_P$1") (pintype "passive"))
      (node (ref "C35") (pin "P$1") (pinfunction "1_P$1") (pintype "passive"))
      (node (ref "C48") (pin "1") (pinfunction "1_1") (pintype "passive"))
      (node (ref "C49") (pin "P$1") (pinfunction "1_P$1") (pintype "passive"))
      (node (ref "C54") (pin "P$2") (pinfunction "2_P$2") (pintype "passive"))
      (node (ref "C55") (pin "P$2") (pinfunction "2_P$2") (pintype "passive"))
      (node (ref "C56") (pin "P$2") (pinfunction "2_P$2") (pintype "passive"))
      (node (ref "C58") (pin "P$1") (pinfunction "1_P$1") (pintype "passive"))
      (node (ref "C59") (pin "P$1") (pinfunction "1_P$1") (pintype "passive"))
      (node (ref "C60") (pin "P$1") (pinfunction "1_P$1") (pintype "passive"))
      (node (ref "C61") (pin "P$2") (pinfunction "2_P$2") (pintype "passive"))
      (node (ref "FB2/2") (pin "1") (pinfunction "P$1_1") (pintype "bidirectional"))
      (node (ref "J11") (pin "2") (pinfunction "2_2") (pintype "passive"))
      (node (ref "J11") (pin "4") (pinfunction "4_4") (pintype "passive"))
      (node (ref "J9") (pin "4") (pinfunction "SUPPLY_VOLTAGE_4") (pintype "power_in"))
      (node (ref "L3") (pin "2") (pinfunction "P$2_2") (pintype "bidirectional"))
      (node (ref "R10") (pin "P$1") (pinfunction "1_P$1") (pintype "passive"))
      (node (ref "R11") (pin "P$1") (pinfunction "1_P$1") (pintype "passive"))
      (node (ref "R13") (pin "P$2") (pinfunction "2_P$2") (pintype "passive"))
      (node (ref "R14") (pin "P$1") (pinfunction "1_P$1") (pintype "passive"))
      (node (ref "R18") (pin "P$2") (pinfunction "2_P$2") (pintype "passive"))
      (node (ref "R2") (pin "P$1") (pinfunction "1_P$1") (pintype "passive"))
      (node (ref "R20") (pin "P$1") (pinfunction "1_P$1") (pintype "passive"))
      (node (ref "R21") (pin "P$1") (pinfunction "1_P$1") (pintype "passive"))
      (node (ref "R23") (pin "P$2") (pinfunction "2_P$2") (pintype "passive"))
      (node (ref "R24") (pin "P$2") (pinfunction "2_P$2") (pintype "passive"))
      (node (ref "R26") (pin "P$2") (pinfunction "2_P$2") (pintype "passive"))
      (node (ref "R27") (pin "P$2") (pinfunction "2_P$2") (pintype "passive"))
      (node (ref "R28") (pin "P$2") (pinfunction "2_P$2") (pintype "passive"))
      (node (ref "R29") (pin "P$2") (pinfunction "2_P$2") (pintype "passive"))
      (node (ref "R3") (pin "P$1") (pinfunction "1_P$1") (pintype "passive"))
      (node (ref "R8") (pin "P$1") (pinfunction "1_P$1") (pintype "passive"))
      (node (ref "R9") (pin "P$1") (pinfunction "1_P$1") (pintype "passive"))
      (node (ref "U3") (pin "14") (pinfunction "VDDIO_14") (pintype "power_in"))
      (node (ref "U4") (pin "110") (pinfunction "VCC(IO)5_110") (pintype "bidirectional"))
      (node (ref "U4") (pin "123") (pinfunction "VCC(IO)6_123") (pintype "bidirectional"))
      (node (ref "U4") (pin "138") (pinfunction "VCC(IO)7_138") (pintype "bidirectional"))
      (node (ref "U4") (pin "149") (pinfunction "VCC(IO)8_149") (pintype "bidirectional"))
      (node (ref "U4") (pin "154") (pinfunction "VREFH_154") (pintype "bidirectional"))
      (node (ref "U4") (pin "155") (pinfunction "AVCC0_155") (pintype "bidirectional"))
      (node (ref "U4") (pin "158") (pinfunction "VREFH0_158") (pintype "bidirectional"))
      (node (ref "U4") (pin "171") (pinfunction "VCC(IO)9_171") (pintype "bidirectional"))
      (node (ref "U4") (pin "25") (pinfunction "VCC1_25") (pintype "bidirectional"))
      (node (ref "U4") (pin "26") (pinfunction "AVCC_SUBHS_26") (pintype "bidirectional"))
      (node (ref "U4") (pin "34") (pinfunction "VCC_USBHS_34") (pintype "bidirectional"))
      (node (ref "U4") (pin "48") (pinfunction "VCC_USB_48") (pintype "bidirectional"))
      (node (ref "U4") (pin "61") (pinfunction "VCC(IO)2_61") (pintype "bidirectional"))
      (node (ref "U4") (pin "84") (pinfunction "VCC(IO)3_84") (pintype "bidirectional"))
      (node (ref "U4") (pin "97") (pinfunction "VCC(IO)4_97") (pintype "bidirectional"))
    )
    (net (code "187") (name "VDD5") (class "Default")
      (node (ref "C5") (pin "P$1") (pinfunction "1_P$1") (pintype "passive"))
      (node (ref "C8") (pin "P$1") (pinfunction "1_P$1") (pintype "passive"))
      (node (ref "J1") (pin "5") (pinfunction "5_5") (pintype "passive"))
      (node (ref "J1") (pin "6") (pinfunction "6_6") (pintype "passive"))
      (node (ref "R1") (pin "P$2") (pinfunction "2_P$2") (pintype "passive"))
      (node (ref "R12") (pin "P$2") (pinfunction "2_P$2") (pintype "passive"))
      (node (ref "U2") (pin "4") (pinfunction "VIN_4") (pintype "input"))
    )
    (net (code "188") (name "VDD12") (class "Default")
      (node (ref "J1") (pin "7") (pinfunction "7_7") (pintype "passive"))
      (node (ref "J1") (pin "8") (pinfunction "8_8") (pintype "passive"))
    )
    (net (code "189") (name "VDDIN") (class "Default")
      (node (ref "J1") (pin "3") (pinfunction "3_3") (pintype "passive"))
      (node (ref "J1") (pin "4") (pinfunction "4_4") (pintype "passive"))
      (node (ref "L3") (pin "1") (pinfunction "P$1_1") (pintype "bidirectional"))
    )
    (net (code "190") (name "VDD_1.2") (class "Default")
      (node (ref "C45") (pin "P$1") (pinfunction "1_P$1") (pintype "passive"))
      (node (ref "C46") (pin "P$1") (pinfunction "1_P$1") (pintype "passive"))
      (node (ref "U3") (pin "1") (pinfunction "VDD_1.2_1") (pintype "power_in"))
    )
    (net (code "191") (name "XCIN") (class "Default")
      (node (ref "C50") (pin "P$1") (pinfunction "1_P$1") (pintype "passive"))
      (node (ref "U4") (pin "20") (pinfunction "XCIN_20") (pintype "bidirectional"))
      (node (ref "X3") (pin "P$1") (pinfunction "P$1_P$1") (pintype "bidirectional"))
    )
    (net (code "192") (name "XCOUT") (class "Default")
      (node (ref "C51") (pin "P$1") (pinfunction "1_P$1") (pintype "passive"))
      (node (ref "U4") (pin "21") (pinfunction "XCOUT_21") (pintype "bidirectional"))
      (node (ref "X3") (pin "P$2") (pinfunction "P$2_P$2") (pintype "bidirectional"))
    )
    (net (code "193") (name "XII") (class "Default")
      (node (ref "C42") (pin "P$1") (pinfunction "1_P$1") (pintype "passive"))
      (node (ref "U$3") (pin "1") (pinfunction "1_1") (pintype "bidirectional"))
      (node (ref "U3") (pin "8") (pinfunction "XI_8") (pintype "input"))
    )
    (net (code "194") (name "XOO") (class "Default")
      (node (ref "C41") (pin "P$1") (pinfunction "1_P$1") (pintype "passive"))
      (node (ref "U$3") (pin "3") (pinfunction "3_3") (pintype "bidirectional"))
      (node (ref "U3") (pin "7") (pinfunction "XO_7") (pintype "output"))
    )
    (net (code "195") (name "XTAL1") (class "Default")
      (node (ref "C52") (pin "P$1") (pinfunction "1_P$1") (pintype "passive"))
      (node (ref "U4") (pin "23") (pinfunction "P2_13/XTAL_23") (pintype "bidirectional"))
      (node (ref "X4") (pin "1") (pinfunction "1_1") (pintype "bidirectional"))
    )
    (net (code "196") (name "XTAL2") (class "Default")
      (node (ref "C53") (pin "P$1") (pinfunction "1_P$1") (pintype "passive"))
      (node (ref "U4") (pin "24") (pinfunction "P2_12/EXTAL_24") (pintype "bidirectional"))
      (node (ref "X4") (pin "3") (pinfunction "3_3") (pintype "bidirectional"))
    )
    (net (code "197") (name "unconnected-(U4-VBAT-Pad18)") (class "Default")
      (node (ref "U4") (pin "18") (pinfunction "VBAT_18") (pintype "bidirectional"))
    )
  )
)
